# R211J.net
KiCad netlist of a schematic drawn in EAGLE
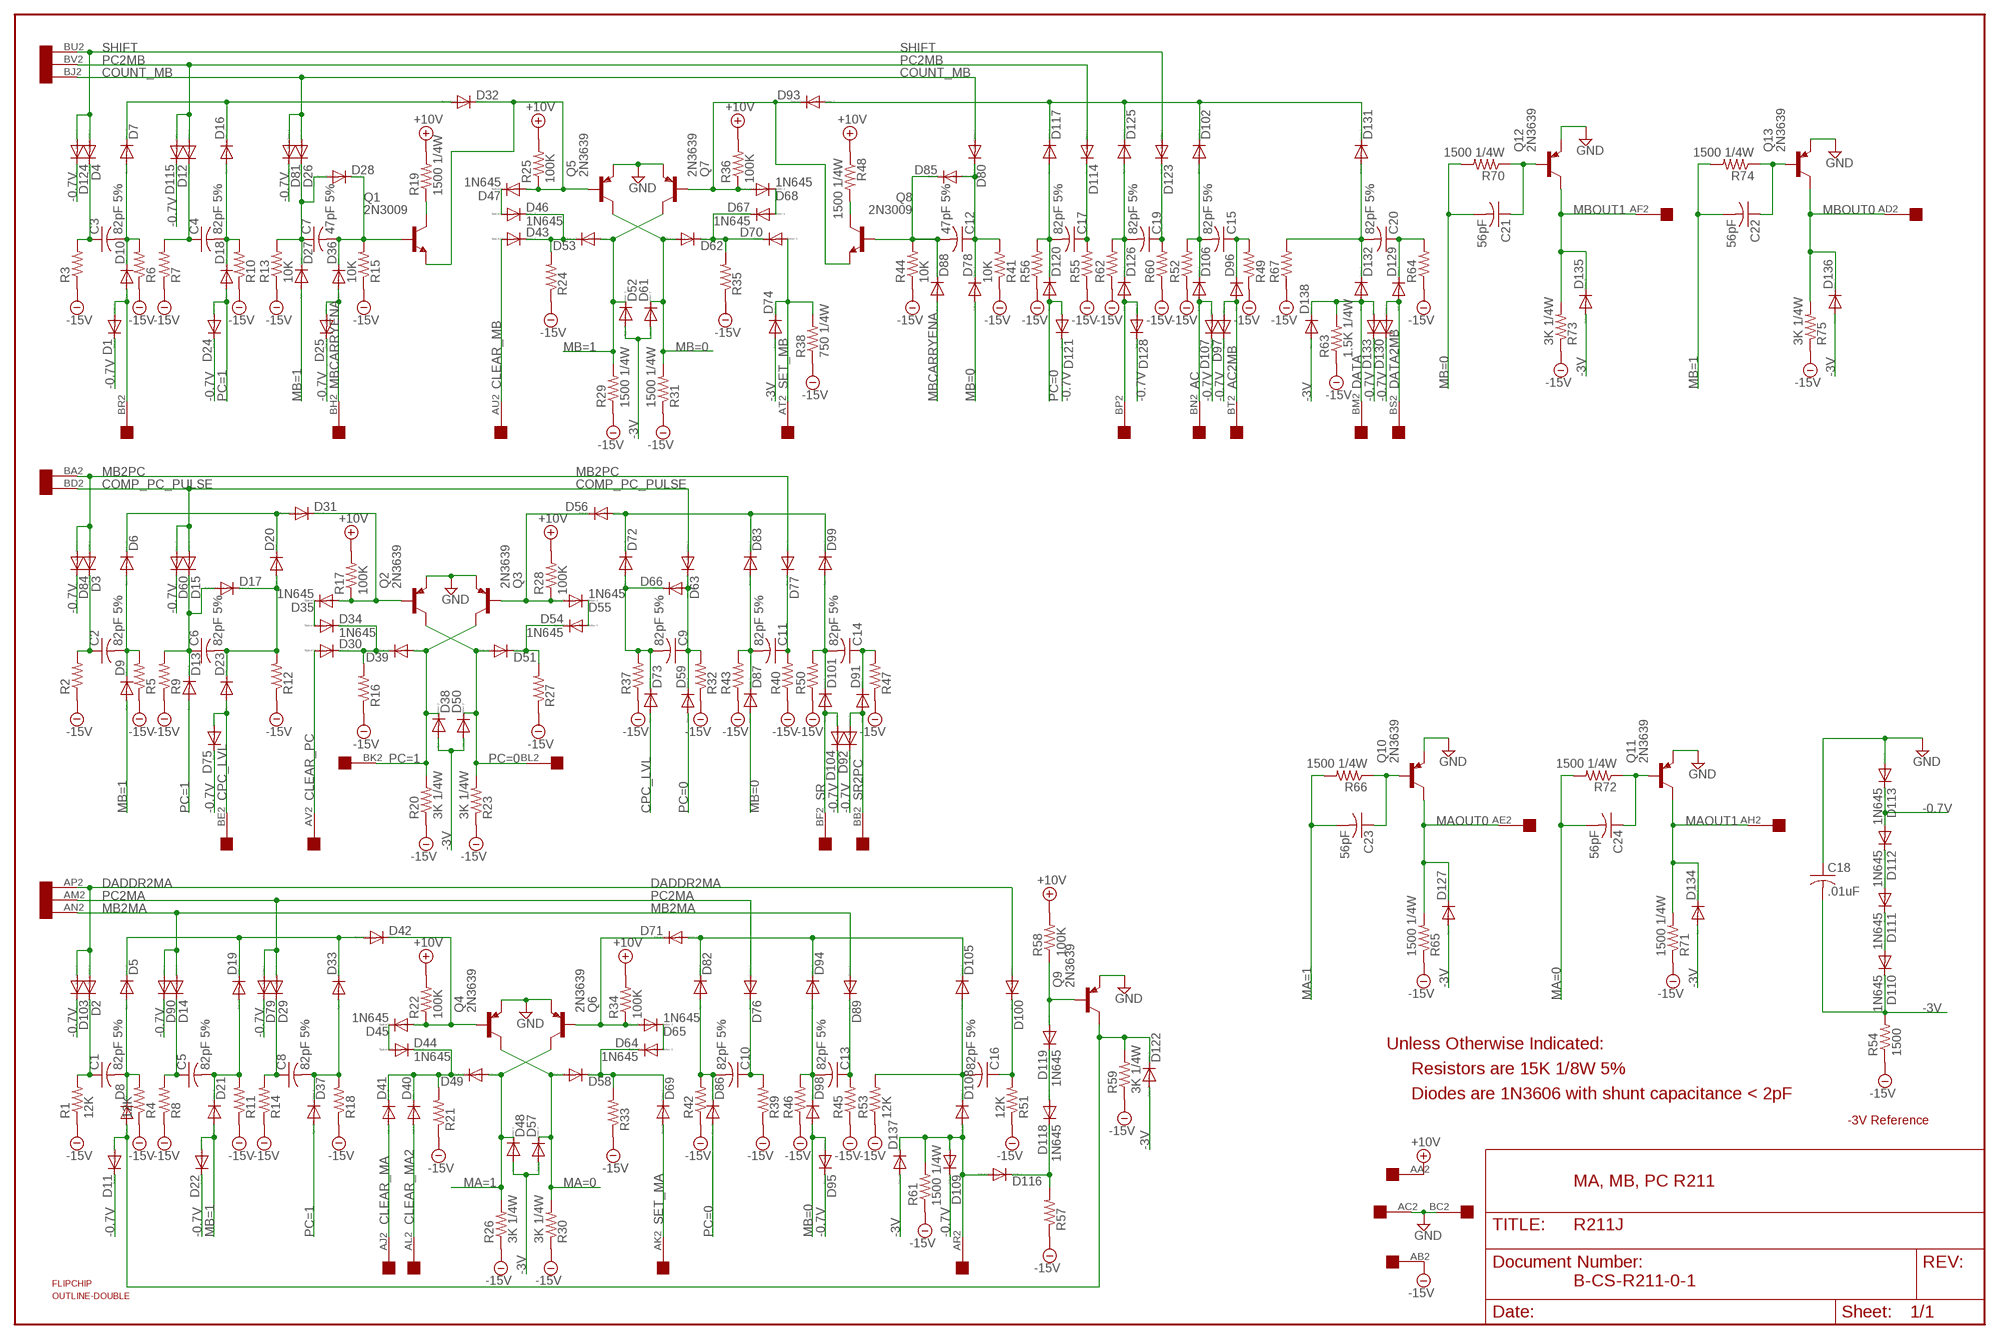
[diagram p0: schematic, sheet 1]

(export (version "E")
  (design (tool "Eeschema 10.0.6"))
  (components
    (comp (ref "C1")
      (value "82pF 5%")
      (footprint "eagle-import:C050-025X075")
      (libsource (lib "eagle-import") (part "C-US050-025X075"))
    )
    (comp (ref "C2")
      (value "82pF 5%")
      (footprint "eagle-import:C050-025X075")
      (libsource (lib "eagle-import") (part "C-US050-025X075"))
    )
    (comp (ref "C3")
      (value "82pF 5%")
      (footprint "eagle-import:C050-025X075")
      (libsource (lib "eagle-import") (part "C-US050-025X075"))
    )
    (comp (ref "C4")
      (value "82pF 5%")
      (footprint "eagle-import:C050-025X075")
      (libsource (lib "eagle-import") (part "C-US050-025X075"))
    )
    (comp (ref "C5")
      (value "82pF 5%")
      (footprint "eagle-import:C050-025X075")
      (libsource (lib "eagle-import") (part "C-US050-025X075"))
    )
    (comp (ref "C6")
      (value "82pF 5%")
      (footprint "eagle-import:C050-025X075")
      (libsource (lib "eagle-import") (part "C-US050-025X075"))
    )
    (comp (ref "C7")
      (value "47pF 5%")
      (footprint "eagle-import:C050-025X075")
      (libsource (lib "eagle-import") (part "C-US050-025X075"))
    )
    (comp (ref "C8")
      (value "82pF 5%")
      (footprint "eagle-import:C050-025X075")
      (libsource (lib "eagle-import") (part "C-US050-025X075"))
    )
    (comp (ref "C9")
      (value "82pF 5%")
      (footprint "eagle-import:C050-025X075")
      (libsource (lib "eagle-import") (part "C-US050-025X075"))
    )
    (comp (ref "C10")
      (value "82pF 5%")
      (footprint "eagle-import:C050-025X075")
      (libsource (lib "eagle-import") (part "C-US050-025X075"))
    )
    (comp (ref "C11")
      (value "82pF 5%")
      (footprint "eagle-import:C050-025X075")
      (libsource (lib "eagle-import") (part "C-US050-025X075"))
    )
    (comp (ref "C12")
      (value "47pF 5%")
      (footprint "eagle-import:C050-025X075")
      (libsource (lib "eagle-import") (part "C-US050-025X075"))
    )
    (comp (ref "C13")
      (value "82pF 5%")
      (footprint "eagle-import:C050-025X075")
      (libsource (lib "eagle-import") (part "C-US050-025X075"))
    )
    (comp (ref "C14")
      (value "82pF 5%")
      (footprint "eagle-import:C050-025X075")
      (libsource (lib "eagle-import") (part "C-US050-025X075"))
    )
    (comp (ref "C15")
      (value "82pF 5%")
      (footprint "eagle-import:C050-025X075")
      (libsource (lib "eagle-import") (part "C-US050-025X075"))
    )
    (comp (ref "C16")
      (value "82pF 5%")
      (footprint "eagle-import:C050-025X075")
      (libsource (lib "eagle-import") (part "C-US050-025X075"))
    )
    (comp (ref "C17")
      (value "82pF 5%")
      (footprint "eagle-import:C050-025X075")
      (libsource (lib "eagle-import") (part "C-US050-025X075"))
    )
    (comp (ref "C18")
      (value ".01uF")
      (footprint "eagle-import:C050-025X075")
      (libsource (lib "eagle-import") (part "C-US050-025X075"))
    )
    (comp (ref "C19")
      (value "82pF 5%")
      (footprint "eagle-import:C050-025X075")
      (libsource (lib "eagle-import") (part "C-US050-025X075"))
    )
    (comp (ref "C20")
      (value "82pF 5%")
      (footprint "eagle-import:C050-025X075")
      (libsource (lib "eagle-import") (part "C-US050-025X075"))
    )
    (comp (ref "C21")
      (value "56pF")
      (footprint "eagle-import:C050-025X075")
      (libsource (lib "eagle-import") (part "C-US050-025X075"))
    )
    (comp (ref "C22")
      (value "56pF")
      (footprint "eagle-import:C050-025X075")
      (libsource (lib "eagle-import") (part "C-US050-025X075"))
    )
    (comp (ref "C23")
      (value "56pF")
      (footprint "eagle-import:C050-025X075")
      (libsource (lib "eagle-import") (part "C-US050-025X075"))
    )
    (comp (ref "C24")
      (value "56pF")
      (footprint "eagle-import:C050-025X075")
      (libsource (lib "eagle-import") (part "C-US050-025X075"))
    )
    (comp (ref "D1")
      (value "1N4148DO35-10")
      (footprint "eagle-import:DO35-10")
      (libsource (lib "eagle-import") (part "1N4148DO35-10"))
    )
    (comp (ref "D2")
      (value "1N4148DO35-10")
      (footprint "eagle-import:DO35-10")
      (libsource (lib "eagle-import") (part "1N4148DO35-10"))
    )
    (comp (ref "D3")
      (value "1N4148DO35-10")
      (footprint "eagle-import:DO35-10")
      (libsource (lib "eagle-import") (part "1N4148DO35-10"))
    )
    (comp (ref "D4")
      (value "1N4148DO35-10")
      (footprint "eagle-import:DO35-10")
      (libsource (lib "eagle-import") (part "1N4148DO35-10"))
    )
    (comp (ref "D5")
      (value "1N4148DO35-10")
      (footprint "eagle-import:DO35-10")
      (libsource (lib "eagle-import") (part "1N4148DO35-10"))
    )
    (comp (ref "D6")
      (value "1N4148DO35-10")
      (footprint "eagle-import:DO35-10")
      (libsource (lib "eagle-import") (part "1N4148DO35-10"))
    )
    (comp (ref "D7")
      (value "1N4148DO35-10")
      (footprint "eagle-import:DO35-10")
      (libsource (lib "eagle-import") (part "1N4148DO35-10"))
    )
    (comp (ref "D8")
      (value "1N4148DO35-10")
      (footprint "eagle-import:DO35-10")
      (libsource (lib "eagle-import") (part "1N4148DO35-10"))
    )
    (comp (ref "D9")
      (value "1N4148DO35-10")
      (footprint "eagle-import:DO35-10")
      (libsource (lib "eagle-import") (part "1N4148DO35-10"))
    )
    (comp (ref "D10")
      (value "1N4148DO35-10")
      (footprint "eagle-import:DO35-10")
      (libsource (lib "eagle-import") (part "1N4148DO35-10"))
    )
    (comp (ref "D11")
      (value "1N4148DO35-10")
      (footprint "eagle-import:DO35-10")
      (libsource (lib "eagle-import") (part "1N4148DO35-10"))
    )
    (comp (ref "D12")
      (value "1N4148DO35-10")
      (footprint "eagle-import:DO35-10")
      (libsource (lib "eagle-import") (part "1N4148DO35-10"))
    )
    (comp (ref "D13")
      (value "1N4148DO35-10")
      (footprint "eagle-import:DO35-10")
      (libsource (lib "eagle-import") (part "1N4148DO35-10"))
    )
    (comp (ref "D14")
      (value "1N4148DO35-10")
      (footprint "eagle-import:DO35-10")
      (libsource (lib "eagle-import") (part "1N4148DO35-10"))
    )
    (comp (ref "D15")
      (value "1N4148DO35-10")
      (footprint "eagle-import:DO35-10")
      (libsource (lib "eagle-import") (part "1N4148DO35-10"))
    )
    (comp (ref "D16")
      (value "1N4148DO35-10")
      (footprint "eagle-import:DO35-10")
      (libsource (lib "eagle-import") (part "1N4148DO35-10"))
    )
    (comp (ref "D17")
      (value "1N4148DO35-10")
      (footprint "eagle-import:DO35-10")
      (libsource (lib "eagle-import") (part "1N4148DO35-10"))
    )
    (comp (ref "D18")
      (value "1N4148DO35-10")
      (footprint "eagle-import:DO35-10")
      (libsource (lib "eagle-import") (part "1N4148DO35-10"))
    )
    (comp (ref "D19")
      (value "1N4148DO35-10")
      (footprint "eagle-import:DO35-10")
      (libsource (lib "eagle-import") (part "1N4148DO35-10"))
    )
    (comp (ref "D20")
      (value "1N4148DO35-10")
      (footprint "eagle-import:DO35-10")
      (libsource (lib "eagle-import") (part "1N4148DO35-10"))
    )
    (comp (ref "D21")
      (value "1N4148DO35-10")
      (footprint "eagle-import:DO35-10")
      (libsource (lib "eagle-import") (part "1N4148DO35-10"))
    )
    (comp (ref "D22")
      (value "1N4148DO35-10")
      (footprint "eagle-import:DO35-10")
      (libsource (lib "eagle-import") (part "1N4148DO35-10"))
    )
    (comp (ref "D23")
      (value "1N4148DO35-10")
      (footprint "eagle-import:DO35-10")
      (libsource (lib "eagle-import") (part "1N4148DO35-10"))
    )
    (comp (ref "D24")
      (value "1N4148DO35-10")
      (footprint "eagle-import:DO35-10")
      (libsource (lib "eagle-import") (part "1N4148DO35-10"))
    )
    (comp (ref "D25")
      (value "1N4148DO35-10")
      (footprint "eagle-import:DO35-10")
      (libsource (lib "eagle-import") (part "1N4148DO35-10"))
    )
    (comp (ref "D26")
      (value "1N4148DO35-10")
      (footprint "eagle-import:DO35-10")
      (libsource (lib "eagle-import") (part "1N4148DO35-10"))
    )
    (comp (ref "D27")
      (value "1N4148DO35-10")
      (footprint "eagle-import:DO35-10")
      (libsource (lib "eagle-import") (part "1N4148DO35-10"))
    )
    (comp (ref "D28")
      (value "1N4148DO35-10")
      (footprint "eagle-import:DO35-10")
      (libsource (lib "eagle-import") (part "1N4148DO35-10"))
    )
    (comp (ref "D29")
      (value "1N4148DO35-10")
      (footprint "eagle-import:DO35-10")
      (libsource (lib "eagle-import") (part "1N4148DO35-10"))
    )
    (comp (ref "D30")
      (value "1N4148DO35-10")
      (footprint "eagle-import:DO35-10")
      (libsource (lib "eagle-import") (part "1N4148DO35-10"))
    )
    (comp (ref "D31")
      (value "1N4148DO35-10")
      (footprint "eagle-import:DO35-10")
      (libsource (lib "eagle-import") (part "1N4148DO35-10"))
    )
    (comp (ref "D32")
      (value "1N4148DO35-10")
      (footprint "eagle-import:DO35-10")
      (libsource (lib "eagle-import") (part "1N4148DO35-10"))
    )
    (comp (ref "D33")
      (value "1N4148DO35-10")
      (footprint "eagle-import:DO35-10")
      (libsource (lib "eagle-import") (part "1N4148DO35-10"))
    )
    (comp (ref "D34")
      (value "1N645")
      (footprint "eagle-import:DO35-10")
      (libsource (lib "eagle-import") (part "1N4148DO35-10"))
    )
    (comp (ref "D35")
      (value "1N645")
      (footprint "eagle-import:DO35-10")
      (libsource (lib "eagle-import") (part "1N4148DO35-10"))
    )
    (comp (ref "D36")
      (value "1N4148DO35-10")
      (footprint "eagle-import:DO35-10")
      (libsource (lib "eagle-import") (part "1N4148DO35-10"))
    )
    (comp (ref "D37")
      (value "1N4148DO35-10")
      (footprint "eagle-import:DO35-10")
      (libsource (lib "eagle-import") (part "1N4148DO35-10"))
    )
    (comp (ref "D38")
      (value "1N4148DO35-10")
      (footprint "eagle-import:DO35-10")
      (libsource (lib "eagle-import") (part "1N4148DO35-10"))
    )
    (comp (ref "D39")
      (value "1N4148DO35-10")
      (footprint "eagle-import:DO35-10")
      (libsource (lib "eagle-import") (part "1N4148DO35-10"))
    )
    (comp (ref "D40")
      (value "1N4148DO35-10")
      (footprint "eagle-import:DO35-10")
      (libsource (lib "eagle-import") (part "1N4148DO35-10"))
    )
    (comp (ref "D41")
      (value "1N4148DO35-10")
      (footprint "eagle-import:DO35-10")
      (libsource (lib "eagle-import") (part "1N4148DO35-10"))
    )
    (comp (ref "D42")
      (value "1N4148DO35-10")
      (footprint "eagle-import:DO35-10")
      (libsource (lib "eagle-import") (part "1N4148DO35-10"))
    )
    (comp (ref "D43")
      (value "1N4148DO35-10")
      (footprint "eagle-import:DO35-10")
      (libsource (lib "eagle-import") (part "1N4148DO35-10"))
    )
    (comp (ref "D44")
      (value "1N645")
      (footprint "eagle-import:DO35-10")
      (libsource (lib "eagle-import") (part "1N4148DO35-10"))
    )
    (comp (ref "D45")
      (value "1N645")
      (footprint "eagle-import:DO35-10")
      (libsource (lib "eagle-import") (part "1N4148DO35-10"))
    )
    (comp (ref "D46")
      (value "1N645")
      (footprint "eagle-import:DO35-10")
      (libsource (lib "eagle-import") (part "1N4148DO35-10"))
    )
    (comp (ref "D47")
      (value "1N645")
      (footprint "eagle-import:DO35-10")
      (libsource (lib "eagle-import") (part "1N4148DO35-10"))
    )
    (comp (ref "D48")
      (value "1N4148DO35-10")
      (footprint "eagle-import:DO35-10")
      (libsource (lib "eagle-import") (part "1N4148DO35-10"))
    )
    (comp (ref "D49")
      (value "1N4148DO35-10")
      (footprint "eagle-import:DO35-10")
      (libsource (lib "eagle-import") (part "1N4148DO35-10"))
    )
    (comp (ref "D50")
      (value "1N4148DO35-10")
      (footprint "eagle-import:DO35-10")
      (libsource (lib "eagle-import") (part "1N4148DO35-10"))
    )
    (comp (ref "D51")
      (value "1N4148DO35-10")
      (footprint "eagle-import:DO35-10")
      (libsource (lib "eagle-import") (part "1N4148DO35-10"))
    )
    (comp (ref "D52")
      (value "1N4148DO35-10")
      (footprint "eagle-import:DO35-10")
      (libsource (lib "eagle-import") (part "1N4148DO35-10"))
    )
    (comp (ref "D53")
      (value "1N4148DO35-10")
      (footprint "eagle-import:DO35-10")
      (libsource (lib "eagle-import") (part "1N4148DO35-10"))
    )
    (comp (ref "D54")
      (value "1N645")
      (footprint "eagle-import:DO35-10")
      (libsource (lib "eagle-import") (part "1N4148DO35-10"))
    )
    (comp (ref "D55")
      (value "1N645")
      (footprint "eagle-import:DO35-10")
      (libsource (lib "eagle-import") (part "1N4148DO35-10"))
    )
    (comp (ref "D56")
      (value "1N4148DO35-10")
      (footprint "eagle-import:DO35-10")
      (libsource (lib "eagle-import") (part "1N4148DO35-10"))
    )
    (comp (ref "D57")
      (value "1N4148DO35-10")
      (footprint "eagle-import:DO35-10")
      (libsource (lib "eagle-import") (part "1N4148DO35-10"))
    )
    (comp (ref "D58")
      (value "1N4148DO35-10")
      (footprint "eagle-import:DO35-10")
      (libsource (lib "eagle-import") (part "1N4148DO35-10"))
    )
    (comp (ref "D59")
      (value "1N4148DO35-10")
      (footprint "eagle-import:DO35-10")
      (libsource (lib "eagle-import") (part "1N4148DO35-10"))
    )
    (comp (ref "D60")
      (value "1N4148DO35-10")
      (footprint "eagle-import:DO35-10")
      (libsource (lib "eagle-import") (part "1N4148DO35-10"))
    )
    (comp (ref "D61")
      (value "1N4148DO35-10")
      (footprint "eagle-import:DO35-10")
      (libsource (lib "eagle-import") (part "1N4148DO35-10"))
    )
    (comp (ref "D62")
      (value "1N4148DO35-10")
      (footprint "eagle-import:DO35-10")
      (libsource (lib "eagle-import") (part "1N4148DO35-10"))
    )
    (comp (ref "D63")
      (value "1N4148DO35-10")
      (footprint "eagle-import:DO35-10")
      (libsource (lib "eagle-import") (part "1N4148DO35-10"))
    )
    (comp (ref "D64")
      (value "1N645")
      (footprint "eagle-import:DO35-10")
      (libsource (lib "eagle-import") (part "1N4148DO35-10"))
    )
    (comp (ref "D65")
      (value "1N645")
      (footprint "eagle-import:DO35-10")
      (libsource (lib "eagle-import") (part "1N4148DO35-10"))
    )
    (comp (ref "D66")
      (value "1N4148DO35-10")
      (footprint "eagle-import:DO35-10")
      (libsource (lib "eagle-import") (part "1N4148DO35-10"))
    )
    (comp (ref "D67")
      (value "1N645")
      (footprint "eagle-import:DO35-10")
      (libsource (lib "eagle-import") (part "1N4148DO35-10"))
    )
    (comp (ref "D68")
      (value "1N645")
      (footprint "eagle-import:DO35-10")
      (libsource (lib "eagle-import") (part "1N4148DO35-10"))
    )
    (comp (ref "D69")
      (value "1N4148DO35-10")
      (footprint "eagle-import:DO35-10")
      (libsource (lib "eagle-import") (part "1N4148DO35-10"))
    )
    (comp (ref "D70")
      (value "1N4148DO35-10")
      (footprint "eagle-import:DO35-10")
      (libsource (lib "eagle-import") (part "1N4148DO35-10"))
    )
    (comp (ref "D71")
      (value "1N4148DO35-10")
      (footprint "eagle-import:DO35-10")
      (libsource (lib "eagle-import") (part "1N4148DO35-10"))
    )
    (comp (ref "D72")
      (value "1N4148DO35-10")
      (footprint "eagle-import:DO35-10")
      (libsource (lib "eagle-import") (part "1N4148DO35-10"))
    )
    (comp (ref "D73")
      (value "1N4148DO35-10")
      (footprint "eagle-import:DO35-10")
      (libsource (lib "eagle-import") (part "1N4148DO35-10"))
    )
    (comp (ref "D74")
      (value "1N4148DO35-10")
      (footprint "eagle-import:DO35-10")
      (libsource (lib "eagle-import") (part "1N4148DO35-10"))
    )
    (comp (ref "D75")
      (value "1N4148DO35-10")
      (footprint "eagle-import:DO35-10")
      (libsource (lib "eagle-import") (part "1N4148DO35-10"))
    )
    (comp (ref "D76")
      (value "1N4148DO35-10")
      (footprint "eagle-import:DO35-10")
      (libsource (lib "eagle-import") (part "1N4148DO35-10"))
    )
    (comp (ref "D77")
      (value "1N4148DO35-10")
      (footprint "eagle-import:DO35-10")
      (libsource (lib "eagle-import") (part "1N4148DO35-10"))
    )
    (comp (ref "D78")
      (value "1N4148DO35-10")
      (footprint "eagle-import:DO35-10")
      (libsource (lib "eagle-import") (part "1N4148DO35-10"))
    )
    (comp (ref "D79")
      (value "1N4148DO35-10")
      (footprint "eagle-import:DO35-10")
      (libsource (lib "eagle-import") (part "1N4148DO35-10"))
    )
    (comp (ref "D80")
      (value "1N4148DO35-10")
      (footprint "eagle-import:DO35-10")
      (libsource (lib "eagle-import") (part "1N4148DO35-10"))
    )
    (comp (ref "D81")
      (value "1N4148DO35-10")
      (footprint "eagle-import:DO35-10")
      (libsource (lib "eagle-import") (part "1N4148DO35-10"))
    )
    (comp (ref "D82")
      (value "1N4148DO35-10")
      (footprint "eagle-import:DO35-10")
      (libsource (lib "eagle-import") (part "1N4148DO35-10"))
    )
    (comp (ref "D83")
      (value "1N4148DO35-10")
      (footprint "eagle-import:DO35-10")
      (libsource (lib "eagle-import") (part "1N4148DO35-10"))
    )
    (comp (ref "D84")
      (value "1N4148DO35-10")
      (footprint "eagle-import:DO35-10")
      (libsource (lib "eagle-import") (part "1N4148DO35-10"))
    )
    (comp (ref "D85")
      (value "1N4148DO35-10")
      (footprint "eagle-import:DO35-10")
      (libsource (lib "eagle-import") (part "1N4148DO35-10"))
    )
    (comp (ref "D86")
      (value "1N4148DO35-10")
      (footprint "eagle-import:DO35-10")
      (libsource (lib "eagle-import") (part "1N4148DO35-10"))
    )
    (comp (ref "D87")
      (value "1N4148DO35-10")
      (footprint "eagle-import:DO35-10")
      (libsource (lib "eagle-import") (part "1N4148DO35-10"))
    )
    (comp (ref "D88")
      (value "1N4148DO35-10")
      (footprint "eagle-import:DO35-10")
      (libsource (lib "eagle-import") (part "1N4148DO35-10"))
    )
    (comp (ref "D89")
      (value "1N4148DO35-10")
      (footprint "eagle-import:DO35-10")
      (libsource (lib "eagle-import") (part "1N4148DO35-10"))
    )
    (comp (ref "D90")
      (value "1N4148DO35-10")
      (footprint "eagle-import:DO35-10")
      (libsource (lib "eagle-import") (part "1N4148DO35-10"))
    )
    (comp (ref "D91")
      (value "1N4148DO35-10")
      (footprint "eagle-import:DO35-10")
      (libsource (lib "eagle-import") (part "1N4148DO35-10"))
    )
    (comp (ref "D92")
      (value "1N4148DO35-10")
      (footprint "eagle-import:DO35-10")
      (libsource (lib "eagle-import") (part "1N4148DO35-10"))
    )
    (comp (ref "D93")
      (value "1N4148DO35-10")
      (footprint "eagle-import:DO35-10")
      (libsource (lib "eagle-import") (part "1N4148DO35-10"))
    )
    (comp (ref "D94")
      (value "1N4148DO35-10")
      (footprint "eagle-import:DO35-10")
      (libsource (lib "eagle-import") (part "1N4148DO35-10"))
    )
    (comp (ref "D95")
      (value "1N4148DO35-10")
      (footprint "eagle-import:DO35-10")
      (libsource (lib "eagle-import") (part "1N4148DO35-10"))
    )
    (comp (ref "D96")
      (value "1N4148DO35-10")
      (footprint "eagle-import:DO35-10")
      (libsource (lib "eagle-import") (part "1N4148DO35-10"))
    )
    (comp (ref "D97")
      (value "1N4148DO35-10")
      (footprint "eagle-import:DO35-10")
      (libsource (lib "eagle-import") (part "1N4148DO35-10"))
    )
    (comp (ref "D98")
      (value "1N4148DO35-10")
      (footprint "eagle-import:DO35-10")
      (libsource (lib "eagle-import") (part "1N4148DO35-10"))
    )
    (comp (ref "D99")
      (value "1N4148DO35-10")
      (footprint "eagle-import:DO35-10")
      (libsource (lib "eagle-import") (part "1N4148DO35-10"))
    )
    (comp (ref "D100")
      (value "1N4148DO35-10")
      (footprint "eagle-import:DO35-10")
      (libsource (lib "eagle-import") (part "1N4148DO35-10"))
    )
    (comp (ref "D101")
      (value "1N4148DO35-10")
      (footprint "eagle-import:DO35-10")
      (libsource (lib "eagle-import") (part "1N4148DO35-10"))
    )
    (comp (ref "D102")
      (value "1N4148DO35-10")
      (footprint "eagle-import:DO35-10")
      (libsource (lib "eagle-import") (part "1N4148DO35-10"))
    )
    (comp (ref "D103")
      (value "1N4148DO35-10")
      (footprint "eagle-import:DO35-10")
      (libsource (lib "eagle-import") (part "1N4148DO35-10"))
    )
    (comp (ref "D104")
      (value "1N4148DO35-10")
      (footprint "eagle-import:DO35-10")
      (libsource (lib "eagle-import") (part "1N4148DO35-10"))
    )
    (comp (ref "D105")
      (value "1N4148DO35-10")
      (footprint "eagle-import:DO35-10")
      (libsource (lib "eagle-import") (part "1N4148DO35-10"))
    )
    (comp (ref "D106")
      (value "1N4148DO35-10")
      (footprint "eagle-import:DO35-10")
      (libsource (lib "eagle-import") (part "1N4148DO35-10"))
    )
    (comp (ref "D107")
      (value "1N4148DO35-10")
      (footprint "eagle-import:DO35-10")
      (libsource (lib "eagle-import") (part "1N4148DO35-10"))
    )
    (comp (ref "D108")
      (value "1N4148DO35-10")
      (footprint "eagle-import:DO35-10")
      (libsource (lib "eagle-import") (part "1N4148DO35-10"))
    )
    (comp (ref "D109")
      (value "1N4148DO35-10")
      (footprint "eagle-import:DO35-10")
      (libsource (lib "eagle-import") (part "1N4148DO35-10"))
    )
    (comp (ref "D110")
      (value "1N645")
      (footprint "eagle-import:DO35-10")
      (libsource (lib "eagle-import") (part "1N4148DO35-10"))
    )
    (comp (ref "D111")
      (value "1N645")
      (footprint "eagle-import:DO35-10")
      (libsource (lib "eagle-import") (part "1N4148DO35-10"))
    )
    (comp (ref "D112")
      (value "1N645")
      (footprint "eagle-import:DO35-10")
      (libsource (lib "eagle-import") (part "1N4148DO35-10"))
    )
    (comp (ref "D113")
      (value "1N645")
      (footprint "eagle-import:DO35-10")
      (libsource (lib "eagle-import") (part "1N4148DO35-10"))
    )
    (comp (ref "D114")
      (value "1N4148DO35-10")
      (footprint "eagle-import:DO35-10")
      (libsource (lib "eagle-import") (part "1N4148DO35-10"))
    )
    (comp (ref "D115")
      (value "1N4148DO35-10")
      (footprint "eagle-import:DO35-10")
      (libsource (lib "eagle-import") (part "1N4148DO35-10"))
    )
    (comp (ref "D116")
      (value "1N4148DO35-10")
      (footprint "eagle-import:DO35-10")
      (libsource (lib "eagle-import") (part "1N4148DO35-10"))
    )
    (comp (ref "D117")
      (value "1N4148DO35-10")
      (footprint "eagle-import:DO35-10")
      (libsource (lib "eagle-import") (part "1N4148DO35-10"))
    )
    (comp (ref "D118")
      (value "1N645")
      (footprint "eagle-import:DO35-10")
      (libsource (lib "eagle-import") (part "1N4148DO35-10"))
    )
    (comp (ref "D119")
      (value "1N645")
      (footprint "eagle-import:DO35-10")
      (libsource (lib "eagle-import") (part "1N4148DO35-10"))
    )
    (comp (ref "D120")
      (value "1N4148DO35-10")
      (footprint "eagle-import:DO35-10")
      (libsource (lib "eagle-import") (part "1N4148DO35-10"))
    )
    (comp (ref "D121")
      (value "1N4148DO35-10")
      (footprint "eagle-import:DO35-10")
      (libsource (lib "eagle-import") (part "1N4148DO35-10"))
    )
    (comp (ref "D122")
      (value "1N4148DO35-10")
      (footprint "eagle-import:DO35-10")
      (libsource (lib "eagle-import") (part "1N4148DO35-10"))
    )
    (comp (ref "D123")
      (value "1N4148DO35-10")
      (footprint "eagle-import:DO35-10")
      (libsource (lib "eagle-import") (part "1N4148DO35-10"))
    )
    (comp (ref "D124")
      (value "1N4148DO35-10")
      (footprint "eagle-import:DO35-10")
      (libsource (lib "eagle-import") (part "1N4148DO35-10"))
    )
    (comp (ref "D125")
      (value "1N4148DO35-10")
      (footprint "eagle-import:DO35-10")
      (libsource (lib "eagle-import") (part "1N4148DO35-10"))
    )
    (comp (ref "D126")
      (value "1N4148DO35-10")
      (footprint "eagle-import:DO35-10")
      (libsource (lib "eagle-import") (part "1N4148DO35-10"))
    )
    (comp (ref "D127")
      (value "1N4148DO35-10")
      (footprint "eagle-import:DO35-10")
      (libsource (lib "eagle-import") (part "1N4148DO35-10"))
    )
    (comp (ref "D128")
      (value "1N4148DO35-10")
      (footprint "eagle-import:DO35-10")
      (libsource (lib "eagle-import") (part "1N4148DO35-10"))
    )
    (comp (ref "D129")
      (value "1N4148DO35-10")
      (footprint "eagle-import:DO35-10")
      (libsource (lib "eagle-import") (part "1N4148DO35-10"))
    )
    (comp (ref "D130")
      (value "1N4148DO35-10")
      (footprint "eagle-import:DO35-10")
      (libsource (lib "eagle-import") (part "1N4148DO35-10"))
    )
    (comp (ref "D131")
      (value "1N4148DO35-10")
      (footprint "eagle-import:DO35-10")
      (libsource (lib "eagle-import") (part "1N4148DO35-10"))
    )
    (comp (ref "D132")
      (value "1N4148DO35-10")
      (footprint "eagle-import:DO35-10")
      (libsource (lib "eagle-import") (part "1N4148DO35-10"))
    )
    (comp (ref "D133")
      (value "1N4148DO35-10")
      (footprint "eagle-import:DO35-10")
      (libsource (lib "eagle-import") (part "1N4148DO35-10"))
    )
    (comp (ref "D134")
      (value "1N4148DO35-10")
      (footprint "eagle-import:DO35-10")
      (libsource (lib "eagle-import") (part "1N4148DO35-10"))
    )
    (comp (ref "D135")
      (value "1N4148DO35-10")
      (footprint "eagle-import:DO35-10")
      (libsource (lib "eagle-import") (part "1N4148DO35-10"))
    )
    (comp (ref "D136")
      (value "1N4148DO35-10")
      (footprint "eagle-import:DO35-10")
      (libsource (lib "eagle-import") (part "1N4148DO35-10"))
    )
    (comp (ref "D137")
      (value "1N4148DO35-10")
      (footprint "eagle-import:DO35-10")
      (libsource (lib "eagle-import") (part "1N4148DO35-10"))
    )
    (comp (ref "D138")
      (value "1N4148DO35-10")
      (footprint "eagle-import:DO35-10")
      (libsource (lib "eagle-import") (part "1N4148DO35-10"))
    )
    (comp (ref "Q1")
      (value "2N3009")
      (footprint "eagle-import:TO5")
      (libsource (lib "eagle-import") (part "2N2102"))
    )
    (comp (ref "Q2")
      (value "2N3639")
      (footprint "eagle-import:TO39")
      (libsource (lib "eagle-import") (part "2N3637"))
    )
    (comp (ref "Q3")
      (value "2N3639")
      (footprint "eagle-import:TO39")
      (libsource (lib "eagle-import") (part "2N3637"))
    )
    (comp (ref "Q4")
      (value "2N3639")
      (footprint "eagle-import:TO39")
      (libsource (lib "eagle-import") (part "2N3637"))
    )
    (comp (ref "Q5")
      (value "2N3639")
      (footprint "eagle-import:TO39")
      (libsource (lib "eagle-import") (part "2N3637"))
    )
    (comp (ref "Q6")
      (value "2N3639")
      (footprint "eagle-import:TO39")
      (libsource (lib "eagle-import") (part "2N3637"))
    )
    (comp (ref "Q7")
      (value "2N3639")
      (footprint "eagle-import:TO39")
      (libsource (lib "eagle-import") (part "2N3637"))
    )
    (comp (ref "Q8")
      (value "2N3009")
      (footprint "eagle-import:TO5")
      (libsource (lib "eagle-import") (part "2N2102"))
    )
    (comp (ref "Q9")
      (value "2N3639")
      (footprint "eagle-import:TO39")
      (libsource (lib "eagle-import") (part "2N3637"))
    )
    (comp (ref "Q10")
      (value "2N3639")
      (footprint "eagle-import:TO39")
      (libsource (lib "eagle-import") (part "2N3637"))
    )
    (comp (ref "Q11")
      (value "2N3639")
      (footprint "eagle-import:TO39")
      (libsource (lib "eagle-import") (part "2N3637"))
    )
    (comp (ref "Q12")
      (value "2N3639")
      (footprint "eagle-import:TO39")
      (libsource (lib "eagle-import") (part "2N3637"))
    )
    (comp (ref "Q13")
      (value "2N3639")
      (footprint "eagle-import:TO39")
      (libsource (lib "eagle-import") (part "2N3637"))
    )
    (comp (ref "R1")
      (value "12K")
      (footprint "eagle-import:0207_10")
      (libsource (lib "eagle-import") (part "R-US_0207/10"))
    )
    (comp (ref "R2")
      (value "R-US_0207/10")
      (footprint "eagle-import:0207_10")
      (libsource (lib "eagle-import") (part "R-US_0207/10"))
    )
    (comp (ref "R3")
      (value "R-US_0207/10")
      (footprint "eagle-import:0207_10")
      (libsource (lib "eagle-import") (part "R-US_0207/10"))
    )
    (comp (ref "R4")
      (value "12K")
      (footprint "eagle-import:0207_10")
      (libsource (lib "eagle-import") (part "R-US_0207/10"))
    )
    (comp (ref "R5")
      (value "R-US_0207/10")
      (footprint "eagle-import:0207_10")
      (libsource (lib "eagle-import") (part "R-US_0207/10"))
    )
    (comp (ref "R6")
      (value "R-US_0207/10")
      (footprint "eagle-import:0207_10")
      (libsource (lib "eagle-import") (part "R-US_0207/10"))
    )
    (comp (ref "R7")
      (value "R-US_0207/10")
      (footprint "eagle-import:0207_10")
      (libsource (lib "eagle-import") (part "R-US_0207/10"))
    )
    (comp (ref "R8")
      (value "R-US_0207/10")
      (footprint "eagle-import:0207_10")
      (libsource (lib "eagle-import") (part "R-US_0207/10"))
    )
    (comp (ref "R9")
      (value "R-US_0207/10")
      (footprint "eagle-import:0207_10")
      (libsource (lib "eagle-import") (part "R-US_0207/10"))
    )
    (comp (ref "R10")
      (value "R-US_0207/10")
      (footprint "eagle-import:0207_10")
      (libsource (lib "eagle-import") (part "R-US_0207/10"))
    )
    (comp (ref "R11")
      (value "R-US_0207/10")
      (footprint "eagle-import:0207_10")
      (libsource (lib "eagle-import") (part "R-US_0207/10"))
    )
    (comp (ref "R12")
      (value "R-US_0207/10")
      (footprint "eagle-import:0207_10")
      (libsource (lib "eagle-import") (part "R-US_0207/10"))
    )
    (comp (ref "R13")
      (value "10K")
      (footprint "eagle-import:0207_10")
      (libsource (lib "eagle-import") (part "R-US_0207/10"))
    )
    (comp (ref "R14")
      (value "R-US_0207/10")
      (footprint "eagle-import:0207_10")
      (libsource (lib "eagle-import") (part "R-US_0207/10"))
    )
    (comp (ref "R15")
      (value "10K")
      (footprint "eagle-import:0207_10")
      (libsource (lib "eagle-import") (part "R-US_0207/10"))
    )
    (comp (ref "R16")
      (value "R-US_0207/10")
      (footprint "eagle-import:0207_10")
      (libsource (lib "eagle-import") (part "R-US_0207/10"))
    )
    (comp (ref "R17")
      (value "100K")
      (footprint "eagle-import:0207_10")
      (libsource (lib "eagle-import") (part "R-US_0207/10"))
    )
    (comp (ref "R18")
      (value "R-US_0207/10")
      (footprint "eagle-import:0207_10")
      (libsource (lib "eagle-import") (part "R-US_0207/10"))
    )
    (comp (ref "R19")
      (value "1500 1/4W")
      (footprint "eagle-import:0207_10")
      (libsource (lib "eagle-import") (part "R-US_0207/10"))
    )
    (comp (ref "R20")
      (value "3K 1/4W")
      (footprint "eagle-import:0207_10")
      (libsource (lib "eagle-import") (part "R-US_0207/10"))
    )
    (comp (ref "R21")
      (value "R-US_0207/10")
      (footprint "eagle-import:0207_10")
      (libsource (lib "eagle-import") (part "R-US_0207/10"))
    )
    (comp (ref "R22")
      (value "100K")
      (footprint "eagle-import:0207_10")
      (libsource (lib "eagle-import") (part "R-US_0207/10"))
    )
    (comp (ref "R23")
      (value "3K 1/4W")
      (footprint "eagle-import:0207_10")
      (libsource (lib "eagle-import") (part "R-US_0207/10"))
    )
    (comp (ref "R24")
      (value "R-US_0207/10")
      (footprint "eagle-import:0207_10")
      (libsource (lib "eagle-import") (part "R-US_0207/10"))
    )
    (comp (ref "R25")
      (value "100K")
      (footprint "eagle-import:0207_10")
      (libsource (lib "eagle-import") (part "R-US_0207/10"))
    )
    (comp (ref "R26")
      (value "3K 1/4W")
      (footprint "eagle-import:0207_10")
      (libsource (lib "eagle-import") (part "R-US_0207/10"))
    )
    (comp (ref "R27")
      (value "R-US_0207/10")
      (footprint "eagle-import:0207_10")
      (libsource (lib "eagle-import") (part "R-US_0207/10"))
    )
    (comp (ref "R28")
      (value "100K")
      (footprint "eagle-import:0207_10")
      (libsource (lib "eagle-import") (part "R-US_0207/10"))
    )
    (comp (ref "R29")
      (value "1500 1/4W")
      (footprint "eagle-import:0207_10")
      (libsource (lib "eagle-import") (part "R-US_0207/10"))
    )
    (comp (ref "R30")
      (value "3K 1/4W")
      (footprint "eagle-import:0207_10")
      (libsource (lib "eagle-import") (part "R-US_0207/10"))
    )
    (comp (ref "R31")
      (value "1500 1/4W")
      (footprint "eagle-import:0207_10")
      (libsource (lib "eagle-import") (part "R-US_0207/10"))
    )
    (comp (ref "R32")
      (value "R-US_0207/10")
      (footprint "eagle-import:0207_10")
      (libsource (lib "eagle-import") (part "R-US_0207/10"))
    )
    (comp (ref "R33")
      (value "R-US_0207/10")
      (footprint "eagle-import:0207_10")
      (libsource (lib "eagle-import") (part "R-US_0207/10"))
    )
    (comp (ref "R34")
      (value "100K")
      (footprint "eagle-import:0207_10")
      (libsource (lib "eagle-import") (part "R-US_0207/10"))
    )
    (comp (ref "R35")
      (value "R-US_0207/10")
      (footprint "eagle-import:0207_10")
      (libsource (lib "eagle-import") (part "R-US_0207/10"))
    )
    (comp (ref "R36")
      (value "100K")
      (footprint "eagle-import:0207_10")
      (libsource (lib "eagle-import") (part "R-US_0207/10"))
    )
    (comp (ref "R37")
      (value "R-US_0207/10")
      (footprint "eagle-import:0207_10")
      (libsource (lib "eagle-import") (part "R-US_0207/10"))
    )
    (comp (ref "R38")
      (value "750 1/4W")
      (footprint "eagle-import:0207_10")
      (libsource (lib "eagle-import") (part "R-US_0207/10"))
    )
    (comp (ref "R39")
      (value "R-US_0207/10")
      (footprint "eagle-import:0207_10")
      (libsource (lib "eagle-import") (part "R-US_0207/10"))
    )
    (comp (ref "R40")
      (value "R-US_0207/10")
      (footprint "eagle-import:0207_10")
      (libsource (lib "eagle-import") (part "R-US_0207/10"))
    )
    (comp (ref "R41")
      (value "10K")
      (footprint "eagle-import:0207_10")
      (libsource (lib "eagle-import") (part "R-US_0207/10"))
    )
    (comp (ref "R42")
      (value "R-US_0207/10")
      (footprint "eagle-import:0207_10")
      (libsource (lib "eagle-import") (part "R-US_0207/10"))
    )
    (comp (ref "R43")
      (value "R-US_0207/10")
      (footprint "eagle-import:0207_10")
      (libsource (lib "eagle-import") (part "R-US_0207/10"))
    )
    (comp (ref "R44")
      (value "10K")
      (footprint "eagle-import:0207_10")
      (libsource (lib "eagle-import") (part "R-US_0207/10"))
    )
    (comp (ref "R45")
      (value "R-US_0207/10")
      (footprint "eagle-import:0207_10")
      (libsource (lib "eagle-import") (part "R-US_0207/10"))
    )
    (comp (ref "R46")
      (value "R-US_0207/10")
      (footprint "eagle-import:0207_10")
      (libsource (lib "eagle-import") (part "R-US_0207/10"))
    )
    (comp (ref "R47")
      (value "R-US_0207/10")
      (footprint "eagle-import:0207_10")
      (libsource (lib "eagle-import") (part "R-US_0207/10"))
    )
    (comp (ref "R48")
      (value "1500 1/4W")
      (footprint "eagle-import:0207_10")
      (libsource (lib "eagle-import") (part "R-US_0207/10"))
    )
    (comp (ref "R49")
      (value "R-US_0207/10")
      (footprint "eagle-import:0207_10")
      (libsource (lib "eagle-import") (part "R-US_0207/10"))
    )
    (comp (ref "R50")
      (value "R-US_0207/10")
      (footprint "eagle-import:0207_10")
      (libsource (lib "eagle-import") (part "R-US_0207/10"))
    )
    (comp (ref "R51")
      (value "12K")
      (footprint "eagle-import:0207_10")
      (libsource (lib "eagle-import") (part "R-US_0207/10"))
    )
    (comp (ref "R52")
      (value "R-US_0207/10")
      (footprint "eagle-import:0207_10")
      (libsource (lib "eagle-import") (part "R-US_0207/10"))
    )
    (comp (ref "R53")
      (value "12K")
      (footprint "eagle-import:0207_10")
      (libsource (lib "eagle-import") (part "R-US_0207/10"))
    )
    (comp (ref "R54")
      (value "1500")
      (footprint "eagle-import:0207_10")
      (libsource (lib "eagle-import") (part "R-US_0207/10"))
    )
    (comp (ref "R55")
      (value "R-US_0207/10")
      (footprint "eagle-import:0207_10")
      (libsource (lib "eagle-import") (part "R-US_0207/10"))
    )
    (comp (ref "R56")
      (value "R-US_0207/10")
      (footprint "eagle-import:0207_10")
      (libsource (lib "eagle-import") (part "R-US_0207/10"))
    )
    (comp (ref "R57")
      (value "R-US_0207/10")
      (footprint "eagle-import:0207_10")
      (libsource (lib "eagle-import") (part "R-US_0207/10"))
    )
    (comp (ref "R58")
      (value "100K")
      (footprint "eagle-import:0207_10")
      (libsource (lib "eagle-import") (part "R-US_0207/10"))
    )
    (comp (ref "R59")
      (value "3K 1/4W")
      (footprint "eagle-import:0207_10")
      (libsource (lib "eagle-import") (part "R-US_0207/10"))
    )
    (comp (ref "R60")
      (value "R-US_0207/10")
      (footprint "eagle-import:0207_10")
      (libsource (lib "eagle-import") (part "R-US_0207/10"))
    )
    (comp (ref "R61")
      (value "1500 1/4W")
      (footprint "eagle-import:0207_10")
      (libsource (lib "eagle-import") (part "R-US_0207/10"))
    )
    (comp (ref "R62")
      (value "R-US_0207/10")
      (footprint "eagle-import:0207_10")
      (libsource (lib "eagle-import") (part "R-US_0207/10"))
    )
    (comp (ref "R63")
      (value "1.5K 1/4W")
      (footprint "eagle-import:0207_10")
      (libsource (lib "eagle-import") (part "R-US_0207/10"))
    )
    (comp (ref "R64")
      (value "R-US_0207/10")
      (footprint "eagle-import:0207_10")
      (libsource (lib "eagle-import") (part "R-US_0207/10"))
    )
    (comp (ref "R65")
      (value "1500 1/4W")
      (footprint "eagle-import:0207_10")
      (libsource (lib "eagle-import") (part "R-US_0207/10"))
    )
    (comp (ref "R66")
      (value "1500 1/4W")
      (footprint "eagle-import:0207_10")
      (libsource (lib "eagle-import") (part "R-US_0207/10"))
    )
    (comp (ref "R67")
      (value "R-US_0207/10")
      (footprint "eagle-import:0207_10")
      (libsource (lib "eagle-import") (part "R-US_0207/10"))
    )
    (comp (ref "R70")
      (value "1500 1/4W")
      (footprint "eagle-import:0207_10")
      (libsource (lib "eagle-import") (part "R-US_0207/10"))
    )
    (comp (ref "R71")
      (value "1500 1/4W")
      (footprint "eagle-import:0207_10")
      (libsource (lib "eagle-import") (part "R-US_0207/10"))
    )
    (comp (ref "R72")
      (value "1500 1/4W")
      (footprint "eagle-import:0207_10")
      (libsource (lib "eagle-import") (part "R-US_0207/10"))
    )
    (comp (ref "R73")
      (value "3K 1/4W")
      (footprint "eagle-import:0207_10")
      (libsource (lib "eagle-import") (part "R-US_0207/10"))
    )
    (comp (ref "R74")
      (value "1500 1/4W")
      (footprint "eagle-import:0207_10")
      (libsource (lib "eagle-import") (part "R-US_0207/10"))
    )
    (comp (ref "R75")
      (value "3K 1/4W")
      (footprint "eagle-import:0207_10")
      (libsource (lib "eagle-import") (part "R-US_0207/10"))
    )
    (comp (ref "U$1")
      (value "DOUBLE")
      (footprint "eagle-import:EDGE-CON4")
      (libsource (lib "eagle-import") (part "DOUBLE"))
    )
    (comp (ref "U$2")
      (value "FLIPCHIP")
      (footprint "eagle-import:FLIPCHIP")
      (libsource (lib "eagle-import") (part "FLIPCHIP"))
    )
    (comp (ref "U$3")
      (value "OUTLINE-DOUBLE")
      (footprint "eagle-import:DOUBLE")
      (libsource (lib "eagle-import") (part "OUTLINE-DOUBLE"))
    )
  )
  (nets
    (net (code "1") (name "+10V") (class "Default")
      (node (ref "R17") (pin "2") (pinfunction "2_2") (pintype "passive"))
      (node (ref "R19") (pin "2") (pinfunction "2_2") (pintype "passive"))
      (node (ref "R22") (pin "2") (pinfunction "2_2") (pintype "passive"))
      (node (ref "R25") (pin "2") (pinfunction "2_2") (pintype "passive"))
      (node (ref "R28") (pin "2") (pinfunction "2_2") (pintype "passive"))
      (node (ref "R34") (pin "2") (pinfunction "2_2") (pintype "passive"))
      (node (ref "R36") (pin "2") (pinfunction "2_2") (pintype "passive"))
      (node (ref "R48") (pin "1") (pinfunction "1_1") (pintype "passive"))
      (node (ref "R58") (pin "2") (pinfunction "2_2") (pintype "passive"))
      (node (ref "U$1") (pin "AA2") (pinfunction "1_AA2") (pintype "bidirectional"))
    )
    (net (code "2") (name "-15V") (class "Default")
      (node (ref "R1") (pin "1") (pinfunction "1_1") (pintype "passive"))
      (node (ref "R10") (pin "1") (pinfunction "1_1") (pintype "passive"))
      (node (ref "R11") (pin "1") (pinfunction "1_1") (pintype "passive"))
      (node (ref "R12") (pin "1") (pinfunction "1_1") (pintype "passive"))
      (node (ref "R13") (pin "1") (pinfunction "1_1") (pintype "passive"))
      (node (ref "R14") (pin "1") (pinfunction "1_1") (pintype "passive"))
      (node (ref "R15") (pin "1") (pinfunction "1_1") (pintype "passive"))
      (node (ref "R16") (pin "1") (pinfunction "1_1") (pintype "passive"))
      (node (ref "R18") (pin "1") (pinfunction "1_1") (pintype "passive"))
      (node (ref "R2") (pin "1") (pinfunction "1_1") (pintype "passive"))
      (node (ref "R20") (pin "1") (pinfunction "1_1") (pintype "passive"))
      (node (ref "R21") (pin "1") (pinfunction "1_1") (pintype "passive"))
      (node (ref "R23") (pin "1") (pinfunction "1_1") (pintype "passive"))
      (node (ref "R24") (pin "1") (pinfunction "1_1") (pintype "passive"))
      (node (ref "R26") (pin "1") (pinfunction "1_1") (pintype "passive"))
      (node (ref "R27") (pin "1") (pinfunction "1_1") (pintype "passive"))
      (node (ref "R29") (pin "1") (pinfunction "1_1") (pintype "passive"))
      (node (ref "R3") (pin "1") (pinfunction "1_1") (pintype "passive"))
      (node (ref "R30") (pin "1") (pinfunction "1_1") (pintype "passive"))
      (node (ref "R31") (pin "1") (pinfunction "1_1") (pintype "passive"))
      (node (ref "R32") (pin "1") (pinfunction "1_1") (pintype "passive"))
      (node (ref "R33") (pin "1") (pinfunction "1_1") (pintype "passive"))
      (node (ref "R35") (pin "1") (pinfunction "1_1") (pintype "passive"))
      (node (ref "R37") (pin "1") (pinfunction "1_1") (pintype "passive"))
      (node (ref "R38") (pin "1") (pinfunction "1_1") (pintype "passive"))
      (node (ref "R39") (pin "1") (pinfunction "1_1") (pintype "passive"))
      (node (ref "R4") (pin "1") (pinfunction "1_1") (pintype "passive"))
      (node (ref "R40") (pin "1") (pinfunction "1_1") (pintype "passive"))
      (node (ref "R41") (pin "1") (pinfunction "1_1") (pintype "passive"))
      (node (ref "R42") (pin "1") (pinfunction "1_1") (pintype "passive"))
      (node (ref "R43") (pin "1") (pinfunction "1_1") (pintype "passive"))
      (node (ref "R44") (pin "1") (pinfunction "1_1") (pintype "passive"))
      (node (ref "R45") (pin "1") (pinfunction "1_1") (pintype "passive"))
      (node (ref "R46") (pin "1") (pinfunction "1_1") (pintype "passive"))
      (node (ref "R47") (pin "1") (pinfunction "1_1") (pintype "passive"))
      (node (ref "R49") (pin "1") (pinfunction "1_1") (pintype "passive"))
      (node (ref "R5") (pin "1") (pinfunction "1_1") (pintype "passive"))
      (node (ref "R50") (pin "1") (pinfunction "1_1") (pintype "passive"))
      (node (ref "R51") (pin "1") (pinfunction "1_1") (pintype "passive"))
      (node (ref "R52") (pin "1") (pinfunction "1_1") (pintype "passive"))
      (node (ref "R53") (pin "1") (pinfunction "1_1") (pintype "passive"))
      (node (ref "R54") (pin "1") (pinfunction "1_1") (pintype "passive"))
      (node (ref "R55") (pin "1") (pinfunction "1_1") (pintype "passive"))
      (node (ref "R56") (pin "1") (pinfunction "1_1") (pintype "passive"))
      (node (ref "R57") (pin "1") (pinfunction "1_1") (pintype "passive"))
      (node (ref "R59") (pin "1") (pinfunction "1_1") (pintype "passive"))
      (node (ref "R6") (pin "1") (pinfunction "1_1") (pintype "passive"))
      (node (ref "R60") (pin "1") (pinfunction "1_1") (pintype "passive"))
      (node (ref "R61") (pin "1") (pinfunction "1_1") (pintype "passive"))
      (node (ref "R62") (pin "1") (pinfunction "1_1") (pintype "passive"))
      (node (ref "R63") (pin "1") (pinfunction "1_1") (pintype "passive"))
      (node (ref "R64") (pin "1") (pinfunction "1_1") (pintype "passive"))
      (node (ref "R65") (pin "1") (pinfunction "1_1") (pintype "passive"))
      (node (ref "R67") (pin "1") (pinfunction "1_1") (pintype "passive"))
      (node (ref "R7") (pin "1") (pinfunction "1_1") (pintype "passive"))
      (node (ref "R71") (pin "1") (pinfunction "1_1") (pintype "passive"))
      (node (ref "R73") (pin "1") (pinfunction "1_1") (pintype "passive"))
      (node (ref "R75") (pin "1") (pinfunction "1_1") (pintype "passive"))
      (node (ref "R8") (pin "1") (pinfunction "1_1") (pintype "passive"))
      (node (ref "R9") (pin "1") (pinfunction "1_1") (pintype "passive"))
      (node (ref "U$1") (pin "AB2") (pinfunction "1_AB2") (pintype "bidirectional"))
    )
    (net (code "3") (name "/-0.7V") (class "Default")
      (node (ref "D1") (pin "C") (pinfunction "C_C") (pintype "passive"))
      (node (ref "D103") (pin "C") (pinfunction "C_C") (pintype "passive"))
      (node (ref "D104") (pin "C") (pinfunction "C_C") (pintype "passive"))
      (node (ref "D107") (pin "C") (pinfunction "C_C") (pintype "passive"))
      (node (ref "D109") (pin "C") (pinfunction "C_C") (pintype "passive"))
      (node (ref "D11") (pin "C") (pinfunction "C_C") (pintype "passive"))
      (node (ref "D112") (pin "A") (pinfunction "A_A") (pintype "passive"))
      (node (ref "D113") (pin "C") (pinfunction "C_C") (pintype "passive"))
      (node (ref "D115") (pin "C") (pinfunction "C_C") (pintype "passive"))
      (node (ref "D121") (pin "C") (pinfunction "C_C") (pintype "passive"))
      (node (ref "D124") (pin "C") (pinfunction "C_C") (pintype "passive"))
      (node (ref "D128") (pin "C") (pinfunction "C_C") (pintype "passive"))
      (node (ref "D130") (pin "C") (pinfunction "C_C") (pintype "passive"))
      (node (ref "D133") (pin "C") (pinfunction "C_C") (pintype "passive"))
      (node (ref "D22") (pin "C") (pinfunction "C_C") (pintype "passive"))
      (node (ref "D24") (pin "C") (pinfunction "C_C") (pintype "passive"))
      (node (ref "D25") (pin "C") (pinfunction "C_C") (pintype "passive"))
      (node (ref "D60") (pin "C") (pinfunction "C_C") (pintype "passive"))
      (node (ref "D75") (pin "C") (pinfunction "C_C") (pintype "passive"))
      (node (ref "D79") (pin "C") (pinfunction "C_C") (pintype "passive"))
      (node (ref "D81") (pin "C") (pinfunction "C_C") (pintype "passive"))
      (node (ref "D84") (pin "C") (pinfunction "C_C") (pintype "passive"))
      (node (ref "D90") (pin "C") (pinfunction "C_C") (pintype "passive"))
      (node (ref "D92") (pin "C") (pinfunction "C_C") (pintype "passive"))
      (node (ref "D95") (pin "C") (pinfunction "C_C") (pintype "passive"))
      (node (ref "D97") (pin "C") (pinfunction "C_C") (pintype "passive"))
    )
    (net (code "4") (name "/-3V") (class "Default")
      (node (ref "C18") (pin "2") (pinfunction "2_2") (pintype "passive"))
      (node (ref "D110") (pin "C") (pinfunction "C_C") (pintype "passive"))
      (node (ref "D122") (pin "A") (pinfunction "A_A") (pintype "passive"))
      (node (ref "D127") (pin "A") (pinfunction "A_A") (pintype "passive"))
      (node (ref "D134") (pin "A") (pinfunction "A_A") (pintype "passive"))
      (node (ref "D135") (pin "A") (pinfunction "A_A") (pintype "passive"))
      (node (ref "D136") (pin "A") (pinfunction "A_A") (pintype "passive"))
      (node (ref "D137") (pin "A") (pinfunction "A_A") (pintype "passive"))
      (node (ref "D138") (pin "A") (pinfunction "A_A") (pintype "passive"))
      (node (ref "D38") (pin "A") (pinfunction "A_A") (pintype "passive"))
      (node (ref "D48") (pin "A") (pinfunction "A_A") (pintype "passive"))
      (node (ref "D50") (pin "A") (pinfunction "A_A") (pintype "passive"))
      (node (ref "D52") (pin "A") (pinfunction "A_A") (pintype "passive"))
      (node (ref "D57") (pin "A") (pinfunction "A_A") (pintype "passive"))
      (node (ref "D61") (pin "A") (pinfunction "A_A") (pintype "passive"))
      (node (ref "D74") (pin "A") (pinfunction "A_A") (pintype "passive"))
      (node (ref "R54") (pin "2") (pinfunction "2_2") (pintype "passive"))
    )
    (net (code "5") (name "/AC") (class "Default")
      (node (ref "D106") (pin "A") (pinfunction "A_A") (pintype "passive"))
      (node (ref "D107") (pin "A") (pinfunction "A_A") (pintype "passive"))
      (node (ref "U$1") (pin "BN2") (pinfunction "1_BN2") (pintype "bidirectional"))
    )
    (net (code "6") (name "/AC2MB") (class "Default")
      (node (ref "D96") (pin "A") (pinfunction "A_A") (pintype "passive"))
      (node (ref "D97") (pin "A") (pinfunction "A_A") (pintype "passive"))
      (node (ref "U$1") (pin "BT2") (pinfunction "1_BT2") (pintype "bidirectional"))
    )
    (net (code "7") (name "/CLEAR_MA") (class "Default")
      (node (ref "D41") (pin "A") (pinfunction "A_A") (pintype "passive"))
      (node (ref "U$1") (pin "AJ2") (pinfunction "1_AJ2") (pintype "bidirectional"))
    )
    (net (code "8") (name "/CLEAR_MA2") (class "Default")
      (node (ref "D40") (pin "A") (pinfunction "A_A") (pintype "passive"))
      (node (ref "U$1") (pin "AL2") (pinfunction "1_AL2") (pintype "bidirectional"))
    )
    (net (code "9") (name "/CLEAR_MB") (class "Default")
      (node (ref "D43") (pin "A") (pinfunction "A_A") (pintype "passive"))
      (node (ref "U$1") (pin "AU2") (pinfunction "1_AU2") (pintype "bidirectional"))
    )
    (net (code "10") (name "/CLEAR_PC") (class "Default")
      (node (ref "D30") (pin "A") (pinfunction "A_A") (pintype "passive"))
      (node (ref "U$1") (pin "AV2") (pinfunction "1_AV2") (pintype "bidirectional"))
    )
    (net (code "11") (name "/COMP_PC_PULSE") (class "Default")
      (node (ref "D15") (pin "A") (pinfunction "A_A") (pintype "passive"))
      (node (ref "D60") (pin "A") (pinfunction "A_A") (pintype "passive"))
      (node (ref "D63") (pin "A") (pinfunction "A_A") (pintype "passive"))
      (node (ref "U$1") (pin "BD2") (pinfunction "1_BD2") (pintype "bidirectional"))
    )
    (net (code "12") (name "/COUNT_MB") (class "Default")
      (node (ref "D26") (pin "A") (pinfunction "A_A") (pintype "passive"))
      (node (ref "D80") (pin "A") (pinfunction "A_A") (pintype "passive"))
      (node (ref "D81") (pin "A") (pinfunction "A_A") (pintype "passive"))
      (node (ref "U$1") (pin "BJ2") (pinfunction "1_BJ2") (pintype "bidirectional"))
    )
    (net (code "13") (name "/CPC_LVL") (class "Default")
      (node (ref "D23") (pin "A") (pinfunction "A_A") (pintype "passive"))
      (node (ref "D73") (pin "A") (pinfunction "A_A") (pintype "passive"))
      (node (ref "D75") (pin "A") (pinfunction "A_A") (pintype "passive"))
      (node (ref "U$1") (pin "BE2") (pinfunction "1_BE2") (pintype "bidirectional"))
    )
    (net (code "14") (name "/DADDR2MA") (class "Default")
      (node (ref "D100") (pin "A") (pinfunction "A_A") (pintype "passive"))
      (node (ref "D103") (pin "A") (pinfunction "A_A") (pintype "passive"))
      (node (ref "D2") (pin "A") (pinfunction "A_A") (pintype "passive"))
      (node (ref "U$1") (pin "AP2") (pinfunction "1_AP2") (pintype "bidirectional"))
    )
    (net (code "15") (name "/DATA") (class "Default")
      (node (ref "D132") (pin "A") (pinfunction "A_A") (pintype "passive"))
      (node (ref "D133") (pin "A") (pinfunction "A_A") (pintype "passive"))
      (node (ref "D138") (pin "C") (pinfunction "C_C") (pintype "passive"))
      (node (ref "R63") (pin "2") (pinfunction "2_2") (pintype "passive"))
      (node (ref "U$1") (pin "BM2") (pinfunction "1_BM2") (pintype "bidirectional"))
    )
    (net (code "16") (name "/DATA2MB") (class "Default")
      (node (ref "D129") (pin "A") (pinfunction "A_A") (pintype "passive"))
      (node (ref "D130") (pin "A") (pinfunction "A_A") (pintype "passive"))
      (node (ref "U$1") (pin "BS2") (pinfunction "1_BS2") (pintype "bidirectional"))
    )
    (net (code "17") (name "/MA=0") (class "Default")
      (node (ref "C24") (pin "2") (pinfunction "2_2") (pintype "passive"))
      (node (ref "D57") (pin "C") (pinfunction "C_C") (pintype "passive"))
      (node (ref "D58") (pin "A") (pinfunction "A_A") (pintype "passive"))
      (node (ref "Q4") (pin "3") (pinfunction "C_3") (pintype "passive"))
      (node (ref "R30") (pin "2") (pinfunction "2_2") (pintype "passive"))
      (node (ref "R72") (pin "2") (pinfunction "2_2") (pintype "passive"))
    )
    (net (code "18") (name "/MA=1") (class "Default")
      (node (ref "C23") (pin "2") (pinfunction "2_2") (pintype "passive"))
      (node (ref "D48") (pin "C") (pinfunction "C_C") (pintype "passive"))
      (node (ref "D49") (pin "A") (pinfunction "A_A") (pintype "passive"))
      (node (ref "Q6") (pin "3") (pinfunction "C_3") (pintype "passive"))
      (node (ref "R26") (pin "2") (pinfunction "2_2") (pintype "passive"))
      (node (ref "R66") (pin "2") (pinfunction "2_2") (pintype "passive"))
    )
    (net (code "19") (name "/MAOUT0") (class "Default")
      (node (ref "D127") (pin "C") (pinfunction "C_C") (pintype "passive"))
      (node (ref "Q10") (pin "3") (pinfunction "C_3") (pintype "passive"))
      (node (ref "R65") (pin "2") (pinfunction "2_2") (pintype "passive"))
      (node (ref "U$1") (pin "AE2") (pinfunction "1_AE2") (pintype "bidirectional"))
    )
    (net (code "20") (name "/MAOUT1") (class "Default")
      (node (ref "D134") (pin "C") (pinfunction "C_C") (pintype "passive"))
      (node (ref "Q11") (pin "3") (pinfunction "C_3") (pintype "passive"))
      (node (ref "R71") (pin "2") (pinfunction "2_2") (pintype "passive"))
      (node (ref "U$1") (pin "AH2") (pinfunction "1_AH2") (pintype "bidirectional"))
    )
    (net (code "21") (name "/MB2MA") (class "Default")
      (node (ref "D14") (pin "A") (pinfunction "A_A") (pintype "passive"))
      (node (ref "D89") (pin "A") (pinfunction "A_A") (pintype "passive"))
      (node (ref "D90") (pin "A") (pinfunction "A_A") (pintype "passive"))
      (node (ref "U$1") (pin "AN2") (pinfunction "1_AN2") (pintype "bidirectional"))
    )
    (net (code "22") (name "/MB2PC") (class "Default")
      (node (ref "D3") (pin "A") (pinfunction "A_A") (pintype "passive"))
      (node (ref "D77") (pin "A") (pinfunction "A_A") (pintype "passive"))
      (node (ref "D84") (pin "A") (pinfunction "A_A") (pintype "passive"))
      (node (ref "U$1") (pin "BA2") (pinfunction "1_BA2") (pintype "bidirectional"))
    )
    (net (code "23") (name "/MB=0") (class "Default")
      (node (ref "C21") (pin "2") (pinfunction "2_2") (pintype "passive"))
      (node (ref "D61") (pin "C") (pinfunction "C_C") (pintype "passive"))
      (node (ref "D62") (pin "A") (pinfunction "A_A") (pintype "passive"))
      (node (ref "D78") (pin "A") (pinfunction "A_A") (pintype "passive"))
      (node (ref "D87") (pin "A") (pinfunction "A_A") (pintype "passive"))
      (node (ref "D95") (pin "A") (pinfunction "A_A") (pintype "passive"))
      (node (ref "D98") (pin "A") (pinfunction "A_A") (pintype "passive"))
      (node (ref "Q5") (pin "3") (pinfunction "C_3") (pintype "passive"))
      (node (ref "R31") (pin "2") (pinfunction "2_2") (pintype "passive"))
      (node (ref "R70") (pin "2") (pinfunction "2_2") (pintype "passive"))
    )
    (net (code "24") (name "/MB=1") (class "Default")
      (node (ref "C22") (pin "2") (pinfunction "2_2") (pintype "passive"))
      (node (ref "D21") (pin "A") (pinfunction "A_A") (pintype "passive"))
      (node (ref "D22") (pin "A") (pinfunction "A_A") (pintype "passive"))
      (node (ref "D27") (pin "A") (pinfunction "A_A") (pintype "passive"))
      (node (ref "D52") (pin "C") (pinfunction "C_C") (pintype "passive"))
      (node (ref "D53") (pin "A") (pinfunction "A_A") (pintype "passive"))
      (node (ref "D9") (pin "A") (pinfunction "A_A") (pintype "passive"))
      (node (ref "Q7") (pin "3") (pinfunction "C_3") (pintype "passive"))
      (node (ref "R29") (pin "2") (pinfunction "2_2") (pintype "passive"))
      (node (ref "R74") (pin "2") (pinfunction "2_2") (pintype "passive"))
    )
    (net (code "25") (name "/MBCARRYENA") (class "Default")
      (node (ref "D25") (pin "A") (pinfunction "A_A") (pintype "passive"))
      (node (ref "D36") (pin "A") (pinfunction "A_A") (pintype "passive"))
      (node (ref "D88") (pin "A") (pinfunction "A_A") (pintype "passive"))
      (node (ref "U$1") (pin "BH2") (pinfunction "1_BH2") (pintype "bidirectional"))
    )
    (net (code "26") (name "/MBOUT0") (class "Default")
      (node (ref "D136") (pin "C") (pinfunction "C_C") (pintype "passive"))
      (node (ref "Q13") (pin "3") (pinfunction "C_3") (pintype "passive"))
      (node (ref "R75") (pin "2") (pinfunction "2_2") (pintype "passive"))
      (node (ref "U$1") (pin "AD2") (pinfunction "1_AD2") (pintype "bidirectional"))
    )
    (net (code "27") (name "/MBOUT1") (class "Default")
      (node (ref "D135") (pin "C") (pinfunction "C_C") (pintype "passive"))
      (node (ref "Q12") (pin "3") (pinfunction "C_3") (pintype "passive"))
      (node (ref "R73") (pin "2") (pinfunction "2_2") (pintype "passive"))
      (node (ref "U$1") (pin "AF2") (pinfunction "1_AF2") (pintype "bidirectional"))
    )
    (net (code "28") (name "/PC2MA") (class "Default")
      (node (ref "D29") (pin "A") (pinfunction "A_A") (pintype "passive"))
      (node (ref "D76") (pin "A") (pinfunction "A_A") (pintype "passive"))
      (node (ref "D79") (pin "A") (pinfunction "A_A") (pintype "passive"))
      (node (ref "U$1") (pin "AM2") (pinfunction "1_AM2") (pintype "bidirectional"))
    )
    (net (code "29") (name "/PC2MB") (class "Default")
      (node (ref "D114") (pin "A") (pinfunction "A_A") (pintype "passive"))
      (node (ref "D115") (pin "A") (pinfunction "A_A") (pintype "passive"))
      (node (ref "D12") (pin "A") (pinfunction "A_A") (pintype "passive"))
      (node (ref "U$1") (pin "BV2") (pinfunction "1_BV2") (pintype "bidirectional"))
    )
    (net (code "30") (name "/PC=0") (class "Default")
      (node (ref "D120") (pin "A") (pinfunction "A_A") (pintype "passive"))
      (node (ref "D121") (pin "A") (pinfunction "A_A") (pintype "passive"))
      (node (ref "D50") (pin "C") (pinfunction "C_C") (pintype "passive"))
      (node (ref "D51") (pin "A") (pinfunction "A_A") (pintype "passive"))
      (node (ref "D59") (pin "A") (pinfunction "A_A") (pintype "passive"))
      (node (ref "D86") (pin "A") (pinfunction "A_A") (pintype "passive"))
      (node (ref "Q2") (pin "3") (pinfunction "C_3") (pintype "passive"))
      (node (ref "R23") (pin "2") (pinfunction "2_2") (pintype "passive"))
      (node (ref "U$1") (pin "BL2") (pinfunction "1_BL2") (pintype "bidirectional"))
    )
    (net (code "31") (name "/PC=1") (class "Default")
      (node (ref "D13") (pin "A") (pinfunction "A_A") (pintype "passive"))
      (node (ref "D18") (pin "A") (pinfunction "A_A") (pintype "passive"))
      (node (ref "D24") (pin "A") (pinfunction "A_A") (pintype "passive"))
      (node (ref "D37") (pin "A") (pinfunction "A_A") (pintype "passive"))
      (node (ref "D38") (pin "C") (pinfunction "C_C") (pintype "passive"))
      (node (ref "D39") (pin "A") (pinfunction "A_A") (pintype "passive"))
      (node (ref "Q3") (pin "3") (pinfunction "C_3") (pintype "passive"))
      (node (ref "R20") (pin "2") (pinfunction "2_2") (pintype "passive"))
      (node (ref "U$1") (pin "BK2") (pinfunction "1_BK2") (pintype "bidirectional"))
    )
    (net (code "32") (name "/SET_MA") (class "Default")
      (node (ref "D69") (pin "A") (pinfunction "A_A") (pintype "passive"))
      (node (ref "U$1") (pin "AK2") (pinfunction "1_AK2") (pintype "bidirectional"))
    )
    (net (code "33") (name "/SET_MB") (class "Default")
      (node (ref "D70") (pin "A") (pinfunction "A_A") (pintype "passive"))
      (node (ref "D74") (pin "C") (pinfunction "C_C") (pintype "passive"))
      (node (ref "R38") (pin "2") (pinfunction "2_2") (pintype "passive"))
      (node (ref "U$1") (pin "AT2") (pinfunction "1_AT2") (pintype "bidirectional"))
    )
    (net (code "34") (name "/SHIFT") (class "Default")
      (node (ref "D123") (pin "A") (pinfunction "A_A") (pintype "passive"))
      (node (ref "D124") (pin "A") (pinfunction "A_A") (pintype "passive"))
      (node (ref "D4") (pin "A") (pinfunction "A_A") (pintype "passive"))
      (node (ref "U$1") (pin "BU2") (pinfunction "1_BU2") (pintype "bidirectional"))
    )
    (net (code "35") (name "/SR") (class "Default")
      (node (ref "D101") (pin "A") (pinfunction "A_A") (pintype "passive"))
      (node (ref "D104") (pin "A") (pinfunction "A_A") (pintype "passive"))
      (node (ref "U$1") (pin "BF2") (pinfunction "1_BF2") (pintype "bidirectional"))
    )
    (net (code "36") (name "/SR2PC") (class "Default")
      (node (ref "D91") (pin "A") (pinfunction "A_A") (pintype "passive"))
      (node (ref "D92") (pin "A") (pinfunction "A_A") (pintype "passive"))
      (node (ref "U$1") (pin "BB2") (pinfunction "1_BB2") (pintype "bidirectional"))
    )
    (net (code "37") (name "GND") (class "Default")
      (node (ref "C18") (pin "1") (pinfunction "1_1") (pintype "passive"))
      (node (ref "D113") (pin "A") (pinfunction "A_A") (pintype "passive"))
      (node (ref "Q10") (pin "1") (pinfunction "E_1") (pintype "passive"))
      (node (ref "Q11") (pin "1") (pinfunction "E_1") (pintype "passive"))
      (node (ref "Q12") (pin "1") (pinfunction "E_1") (pintype "passive"))
      (node (ref "Q13") (pin "1") (pinfunction "E_1") (pintype "passive"))
      (node (ref "Q2") (pin "1") (pinfunction "E_1") (pintype "passive"))
      (node (ref "Q3") (pin "1") (pinfunction "E_1") (pintype "passive"))
      (node (ref "Q4") (pin "1") (pinfunction "E_1") (pintype "passive"))
      (node (ref "Q5") (pin "1") (pinfunction "E_1") (pintype "passive"))
      (node (ref "Q6") (pin "1") (pinfunction "E_1") (pintype "passive"))
      (node (ref "Q7") (pin "1") (pinfunction "E_1") (pintype "passive"))
      (node (ref "Q9") (pin "1") (pinfunction "E_1") (pintype "passive"))
      (node (ref "U$1") (pin "AC2") (pinfunction "1_AC2") (pintype "bidirectional"))
      (node (ref "U$1") (pin "BC2") (pinfunction "1_BC2") (pintype "bidirectional"))
    )
    (net (code "38") (name "Net-(C1-Pad1)") (class "Default")
      (node (ref "C1") (pin "1") (pinfunction "1_1") (pintype "passive"))
      (node (ref "D2") (pin "C") (pinfunction "C_C") (pintype "passive"))
      (node (ref "R1") (pin "2") (pinfunction "2_2") (pintype "passive"))
    )
    (net (code "39") (name "Net-(C1-Pad2)") (class "Default")
      (node (ref "C1") (pin "2") (pinfunction "2_2") (pintype "passive"))
      (node (ref "D5") (pin "A") (pinfunction "A_A") (pintype "passive"))
      (node (ref "D8") (pin "C") (pinfunction "C_C") (pintype "passive"))
      (node (ref "R4") (pin "2") (pinfunction "2_2") (pintype "passive"))
    )
    (net (code "40") (name "Net-(C2-Pad1)") (class "Default")
      (node (ref "C2") (pin "1") (pinfunction "1_1") (pintype "passive"))
      (node (ref "D3") (pin "C") (pinfunction "C_C") (pintype "passive"))
      (node (ref "R2") (pin "2") (pinfunction "2_2") (pintype "passive"))
    )
    (net (code "41") (name "Net-(C2-Pad2)") (class "Default")
      (node (ref "C2") (pin "2") (pinfunction "2_2") (pintype "passive"))
      (node (ref "D6") (pin "A") (pinfunction "A_A") (pintype "passive"))
      (node (ref "D9") (pin "C") (pinfunction "C_C") (pintype "passive"))
      (node (ref "R5") (pin "2") (pinfunction "2_2") (pintype "passive"))
    )
    (net (code "42") (name "Net-(C3-Pad1)") (class "Default")
      (node (ref "C3") (pin "1") (pinfunction "1_1") (pintype "passive"))
      (node (ref "D4") (pin "C") (pinfunction "C_C") (pintype "passive"))
      (node (ref "R3") (pin "2") (pinfunction "2_2") (pintype "passive"))
    )
    (net (code "43") (name "Net-(C3-Pad2)") (class "Default")
      (node (ref "C3") (pin "2") (pinfunction "2_2") (pintype "passive"))
      (node (ref "D10") (pin "C") (pinfunction "C_C") (pintype "passive"))
      (node (ref "D7") (pin "A") (pinfunction "A_A") (pintype "passive"))
      (node (ref "R6") (pin "2") (pinfunction "2_2") (pintype "passive"))
    )
    (net (code "44") (name "Net-(C4-Pad1)") (class "Default")
      (node (ref "C4") (pin "1") (pinfunction "1_1") (pintype "passive"))
      (node (ref "D12") (pin "C") (pinfunction "C_C") (pintype "passive"))
      (node (ref "R7") (pin "2") (pinfunction "2_2") (pintype "passive"))
    )
    (net (code "45") (name "Net-(C4-Pad2)") (class "Default")
      (node (ref "C4") (pin "2") (pinfunction "2_2") (pintype "passive"))
      (node (ref "D16") (pin "A") (pinfunction "A_A") (pintype "passive"))
      (node (ref "D18") (pin "C") (pinfunction "C_C") (pintype "passive"))
      (node (ref "R10") (pin "2") (pinfunction "2_2") (pintype "passive"))
    )
    (net (code "46") (name "Net-(C5-Pad1)") (class "Default")
      (node (ref "C5") (pin "1") (pinfunction "1_1") (pintype "passive"))
      (node (ref "D14") (pin "C") (pinfunction "C_C") (pintype "passive"))
      (node (ref "R8") (pin "2") (pinfunction "2_2") (pintype "passive"))
    )
    (net (code "47") (name "Net-(C5-Pad2)") (class "Default")
      (node (ref "C5") (pin "2") (pinfunction "2_2") (pintype "passive"))
      (node (ref "D19") (pin "A") (pinfunction "A_A") (pintype "passive"))
      (node (ref "D21") (pin "C") (pinfunction "C_C") (pintype "passive"))
      (node (ref "R11") (pin "2") (pinfunction "2_2") (pintype "passive"))
    )
    (net (code "48") (name "Net-(C6-Pad1)") (class "Default")
      (node (ref "C6") (pin "1") (pinfunction "1_1") (pintype "passive"))
      (node (ref "D13") (pin "C") (pinfunction "C_C") (pintype "passive"))
      (node (ref "D15") (pin "C") (pinfunction "C_C") (pintype "passive"))
      (node (ref "D17") (pin "A") (pinfunction "A_A") (pintype "passive"))
      (node (ref "R9") (pin "2") (pinfunction "2_2") (pintype "passive"))
    )
    (net (code "49") (name "Net-(C6-Pad2)") (class "Default")
      (node (ref "C6") (pin "2") (pinfunction "2_2") (pintype "passive"))
      (node (ref "D17") (pin "C") (pinfunction "C_C") (pintype "passive"))
      (node (ref "D20") (pin "A") (pinfunction "A_A") (pintype "passive"))
      (node (ref "D23") (pin "C") (pinfunction "C_C") (pintype "passive"))
      (node (ref "R12") (pin "2") (pinfunction "2_2") (pintype "passive"))
    )
    (net (code "50") (name "Net-(C7-Pad1)") (class "Default")
      (node (ref "C7") (pin "1") (pinfunction "1_1") (pintype "passive"))
      (node (ref "D26") (pin "C") (pinfunction "C_C") (pintype "passive"))
      (node (ref "D27") (pin "C") (pinfunction "C_C") (pintype "passive"))
      (node (ref "D28") (pin "A") (pinfunction "A_A") (pintype "passive"))
      (node (ref "R13") (pin "2") (pinfunction "2_2") (pintype "passive"))
    )
    (net (code "51") (name "Net-(C8-Pad1)") (class "Default")
      (node (ref "C8") (pin "1") (pinfunction "1_1") (pintype "passive"))
      (node (ref "D29") (pin "C") (pinfunction "C_C") (pintype "passive"))
      (node (ref "R14") (pin "2") (pinfunction "2_2") (pintype "passive"))
    )
    (net (code "52") (name "Net-(C8-Pad2)") (class "Default")
      (node (ref "C8") (pin "2") (pinfunction "2_2") (pintype "passive"))
      (node (ref "D33") (pin "A") (pinfunction "A_A") (pintype "passive"))
      (node (ref "D37") (pin "C") (pinfunction "C_C") (pintype "passive"))
      (node (ref "R18") (pin "2") (pinfunction "2_2") (pintype "passive"))
    )
    (net (code "53") (name "Net-(C9-Pad1)") (class "Default")
      (node (ref "C9") (pin "1") (pinfunction "1_1") (pintype "passive"))
      (node (ref "D59") (pin "C") (pinfunction "C_C") (pintype "passive"))
      (node (ref "D63") (pin "C") (pinfunction "C_C") (pintype "passive"))
      (node (ref "D66") (pin "A") (pinfunction "A_A") (pintype "passive"))
      (node (ref "R32") (pin "2") (pinfunction "2_2") (pintype "passive"))
    )
    (net (code "54") (name "Net-(C9-Pad2)") (class "Default")
      (node (ref "C9") (pin "2") (pinfunction "2_2") (pintype "passive"))
      (node (ref "D66") (pin "C") (pinfunction "C_C") (pintype "passive"))
      (node (ref "D72") (pin "A") (pinfunction "A_A") (pintype "passive"))
      (node (ref "D73") (pin "C") (pinfunction "C_C") (pintype "passive"))
      (node (ref "R37") (pin "2") (pinfunction "2_2") (pintype "passive"))
    )
    (net (code "55") (name "Net-(C10-Pad1)") (class "Default")
      (node (ref "C10") (pin "1") (pinfunction "1_1") (pintype "passive"))
      (node (ref "D76") (pin "C") (pinfunction "C_C") (pintype "passive"))
      (node (ref "R39") (pin "2") (pinfunction "2_2") (pintype "passive"))
    )
    (net (code "56") (name "Net-(C10-Pad2)") (class "Default")
      (node (ref "C10") (pin "2") (pinfunction "2_2") (pintype "passive"))
      (node (ref "D82") (pin "A") (pinfunction "A_A") (pintype "passive"))
      (node (ref "D86") (pin "C") (pinfunction "C_C") (pintype "passive"))
      (node (ref "R42") (pin "2") (pinfunction "2_2") (pintype "passive"))
    )
    (net (code "57") (name "Net-(C11-Pad1)") (class "Default")
      (node (ref "C11") (pin "1") (pinfunction "1_1") (pintype "passive"))
      (node (ref "D77") (pin "C") (pinfunction "C_C") (pintype "passive"))
      (node (ref "R40") (pin "2") (pinfunction "2_2") (pintype "passive"))
    )
    (net (code "58") (name "Net-(C11-Pad2)") (class "Default")
      (node (ref "C11") (pin "2") (pinfunction "2_2") (pintype "passive"))
      (node (ref "D83") (pin "A") (pinfunction "A_A") (pintype "passive"))
      (node (ref "D87") (pin "C") (pinfunction "C_C") (pintype "passive"))
      (node (ref "R43") (pin "2") (pinfunction "2_2") (pintype "passive"))
    )
    (net (code "59") (name "Net-(C12-Pad1)") (class "Default")
      (node (ref "C12") (pin "1") (pinfunction "1_1") (pintype "passive"))
      (node (ref "D78") (pin "C") (pinfunction "C_C") (pintype "passive"))
      (node (ref "D80") (pin "C") (pinfunction "C_C") (pintype "passive"))
      (node (ref "D85") (pin "A") (pinfunction "A_A") (pintype "passive"))
      (node (ref "R41") (pin "2") (pinfunction "2_2") (pintype "passive"))
    )
    (net (code "60") (name "Net-(C13-Pad1)") (class "Default")
      (node (ref "C13") (pin "1") (pinfunction "1_1") (pintype "passive"))
      (node (ref "D89") (pin "C") (pinfunction "C_C") (pintype "passive"))
      (node (ref "R45") (pin "2") (pinfunction "2_2") (pintype "passive"))
    )
    (net (code "61") (name "Net-(C13-Pad2)") (class "Default")
      (node (ref "C13") (pin "2") (pinfunction "2_2") (pintype "passive"))
      (node (ref "D94") (pin "A") (pinfunction "A_A") (pintype "passive"))
      (node (ref "D98") (pin "C") (pinfunction "C_C") (pintype "passive"))
      (node (ref "R46") (pin "2") (pinfunction "2_2") (pintype "passive"))
    )
    (net (code "62") (name "Net-(C14-Pad1)") (class "Default")
      (node (ref "C14") (pin "1") (pinfunction "1_1") (pintype "passive"))
      (node (ref "D91") (pin "C") (pinfunction "C_C") (pintype "passive"))
      (node (ref "R47") (pin "2") (pinfunction "2_2") (pintype "passive"))
    )
    (net (code "63") (name "Net-(C14-Pad2)") (class "Default")
      (node (ref "C14") (pin "2") (pinfunction "2_2") (pintype "passive"))
      (node (ref "D101") (pin "C") (pinfunction "C_C") (pintype "passive"))
      (node (ref "D99") (pin "A") (pinfunction "A_A") (pintype "passive"))
      (node (ref "R50") (pin "2") (pinfunction "2_2") (pintype "passive"))
    )
    (net (code "64") (name "Net-(C15-Pad1)") (class "Default")
      (node (ref "C15") (pin "1") (pinfunction "1_1") (pintype "passive"))
      (node (ref "D96") (pin "C") (pinfunction "C_C") (pintype "passive"))
      (node (ref "R49") (pin "2") (pinfunction "2_2") (pintype "passive"))
    )
    (net (code "65") (name "Net-(C15-Pad2)") (class "Default")
      (node (ref "C15") (pin "2") (pinfunction "2_2") (pintype "passive"))
      (node (ref "D102") (pin "A") (pinfunction "A_A") (pintype "passive"))
      (node (ref "D106") (pin "C") (pinfunction "C_C") (pintype "passive"))
      (node (ref "R52") (pin "2") (pinfunction "2_2") (pintype "passive"))
    )
    (net (code "66") (name "Net-(C16-Pad1)") (class "Default")
      (node (ref "C16") (pin "1") (pinfunction "1_1") (pintype "passive"))
      (node (ref "D100") (pin "C") (pinfunction "C_C") (pintype "passive"))
      (node (ref "R51") (pin "2") (pinfunction "2_2") (pintype "passive"))
    )
    (net (code "67") (name "Net-(C16-Pad2)") (class "Default")
      (node (ref "C16") (pin "2") (pinfunction "2_2") (pintype "passive"))
      (node (ref "D105") (pin "A") (pinfunction "A_A") (pintype "passive"))
      (node (ref "D108") (pin "C") (pinfunction "C_C") (pintype "passive"))
      (node (ref "R53") (pin "2") (pinfunction "2_2") (pintype "passive"))
    )
    (net (code "68") (name "Net-(C17-Pad1)") (class "Default")
      (node (ref "C17") (pin "1") (pinfunction "1_1") (pintype "passive"))
      (node (ref "D114") (pin "C") (pinfunction "C_C") (pintype "passive"))
      (node (ref "R55") (pin "2") (pinfunction "2_2") (pintype "passive"))
    )
    (net (code "69") (name "Net-(C17-Pad2)") (class "Default")
      (node (ref "C17") (pin "2") (pinfunction "2_2") (pintype "passive"))
      (node (ref "D117") (pin "A") (pinfunction "A_A") (pintype "passive"))
      (node (ref "D120") (pin "C") (pinfunction "C_C") (pintype "passive"))
      (node (ref "R56") (pin "2") (pinfunction "2_2") (pintype "passive"))
    )
    (net (code "70") (name "Net-(C19-Pad1)") (class "Default")
      (node (ref "C19") (pin "1") (pinfunction "1_1") (pintype "passive"))
      (node (ref "D123") (pin "C") (pinfunction "C_C") (pintype "passive"))
      (node (ref "R60") (pin "2") (pinfunction "2_2") (pintype "passive"))
    )
    (net (code "71") (name "Net-(C19-Pad2)") (class "Default")
      (node (ref "C19") (pin "2") (pinfunction "2_2") (pintype "passive"))
      (node (ref "D125") (pin "A") (pinfunction "A_A") (pintype "passive"))
      (node (ref "D126") (pin "C") (pinfunction "C_C") (pintype "passive"))
      (node (ref "R62") (pin "2") (pinfunction "2_2") (pintype "passive"))
    )
    (net (code "72") (name "Net-(C20-Pad1)") (class "Default")
      (node (ref "C20") (pin "1") (pinfunction "1_1") (pintype "passive"))
      (node (ref "D129") (pin "C") (pinfunction "C_C") (pintype "passive"))
      (node (ref "R64") (pin "2") (pinfunction "2_2") (pintype "passive"))
    )
    (net (code "73") (name "Net-(C20-Pad2)") (class "Default")
      (node (ref "C20") (pin "2") (pinfunction "2_2") (pintype "passive"))
      (node (ref "D131") (pin "A") (pinfunction "A_A") (pintype "passive"))
      (node (ref "D132") (pin "C") (pinfunction "C_C") (pintype "passive"))
      (node (ref "R67") (pin "2") (pinfunction "2_2") (pintype "passive"))
    )
    (net (code "74") (name "Net-(D16-PadC)") (class "Default")
      (node (ref "D16") (pin "C") (pinfunction "C_C") (pintype "passive"))
      (node (ref "D32") (pin "A") (pinfunction "A_A") (pintype "passive"))
      (node (ref "D7") (pin "C") (pinfunction "C_C") (pintype "passive"))
    )
    (net (code "75") (name "Net-(D19-PadC)") (class "Default")
      (node (ref "D19") (pin "C") (pinfunction "C_C") (pintype "passive"))
      (node (ref "D33") (pin "C") (pinfunction "C_C") (pintype "passive"))
      (node (ref "D42") (pin "A") (pinfunction "A_A") (pintype "passive"))
      (node (ref "D5") (pin "C") (pinfunction "C_C") (pintype "passive"))
    )
    (net (code "76") (name "Net-(D20-PadC)") (class "Default")
      (node (ref "D20") (pin "C") (pinfunction "C_C") (pintype "passive"))
      (node (ref "D31") (pin "A") (pinfunction "A_A") (pintype "passive"))
      (node (ref "D6") (pin "C") (pinfunction "C_C") (pintype "passive"))
    )
    (net (code "77") (name "Net-(D30-PadC)") (class "Default")
      (node (ref "D30") (pin "C") (pinfunction "C_C") (pintype "passive"))
      (node (ref "D34") (pin "C") (pinfunction "C_C") (pintype "passive"))
      (node (ref "D39") (pin "C") (pinfunction "C_C") (pintype "passive"))
      (node (ref "R16") (pin "2") (pinfunction "2_2") (pintype "passive"))
    )
    (net (code "78") (name "Net-(D34-PadA)") (class "Default")
      (node (ref "D34") (pin "A") (pinfunction "A_A") (pintype "passive"))
      (node (ref "D35") (pin "C") (pinfunction "C_C") (pintype "passive"))
    )
    (net (code "79") (name "Net-(D40-PadC)") (class "Default")
      (node (ref "D40") (pin "C") (pinfunction "C_C") (pintype "passive"))
      (node (ref "D41") (pin "C") (pinfunction "C_C") (pintype "passive"))
      (node (ref "D44") (pin "C") (pinfunction "C_C") (pintype "passive"))
      (node (ref "D49") (pin "C") (pinfunction "C_C") (pintype "passive"))
      (node (ref "R21") (pin "2") (pinfunction "2_2") (pintype "passive"))
    )
    (net (code "80") (name "Net-(D43-PadC)") (class "Default")
      (node (ref "D43") (pin "C") (pinfunction "C_C") (pintype "passive"))
      (node (ref "D46") (pin "C") (pinfunction "C_C") (pintype "passive"))
      (node (ref "D53") (pin "C") (pinfunction "C_C") (pintype "passive"))
      (node (ref "R24") (pin "2") (pinfunction "2_2") (pintype "passive"))
    )
    (net (code "81") (name "Net-(D44-PadA)") (class "Default")
      (node (ref "D44") (pin "A") (pinfunction "A_A") (pintype "passive"))
      (node (ref "D45") (pin "C") (pinfunction "C_C") (pintype "passive"))
    )
    (net (code "82") (name "Net-(D46-PadA)") (class "Default")
      (node (ref "D46") (pin "A") (pinfunction "A_A") (pintype "passive"))
      (node (ref "D47") (pin "C") (pinfunction "C_C") (pintype "passive"))
    )
    (net (code "83") (name "Net-(D51-PadC)") (class "Default")
      (node (ref "D51") (pin "C") (pinfunction "C_C") (pintype "passive"))
      (node (ref "D54") (pin "C") (pinfunction "C_C") (pintype "passive"))
      (node (ref "R27") (pin "2") (pinfunction "2_2") (pintype "passive"))
    )
    (net (code "84") (name "Net-(D54-PadA)") (class "Default")
      (node (ref "D54") (pin "A") (pinfunction "A_A") (pintype "passive"))
      (node (ref "D55") (pin "C") (pinfunction "C_C") (pintype "passive"))
    )
    (net (code "85") (name "Net-(D56-PadA)") (class "Default")
      (node (ref "D56") (pin "A") (pinfunction "A_A") (pintype "passive"))
      (node (ref "D72") (pin "C") (pinfunction "C_C") (pintype "passive"))
      (node (ref "D83") (pin "C") (pinfunction "C_C") (pintype "passive"))
      (node (ref "D99") (pin "C") (pinfunction "C_C") (pintype "passive"))
    )
    (net (code "86") (name "Net-(D58-PadC)") (class "Default")
      (node (ref "D58") (pin "C") (pinfunction "C_C") (pintype "passive"))
      (node (ref "D64") (pin "C") (pinfunction "C_C") (pintype "passive"))
      (node (ref "D69") (pin "C") (pinfunction "C_C") (pintype "passive"))
      (node (ref "R33") (pin "2") (pinfunction "2_2") (pintype "passive"))
    )
    (net (code "87") (name "Net-(D62-PadC)") (class "Default")
      (node (ref "D62") (pin "C") (pinfunction "C_C") (pintype "passive"))
      (node (ref "D67") (pin "C") (pinfunction "C_C") (pintype "passive"))
      (node (ref "D70") (pin "C") (pinfunction "C_C") (pintype "passive"))
      (node (ref "R35") (pin "2") (pinfunction "2_2") (pintype "passive"))
    )
    (net (code "88") (name "Net-(D64-PadA)") (class "Default")
      (node (ref "D64") (pin "A") (pinfunction "A_A") (pintype "passive"))
      (node (ref "D65") (pin "C") (pinfunction "C_C") (pintype "passive"))
    )
    (net (code "89") (name "Net-(D67-PadA)") (class "Default")
      (node (ref "D67") (pin "A") (pinfunction "A_A") (pintype "passive"))
      (node (ref "D68") (pin "C") (pinfunction "C_C") (pintype "passive"))
    )
    (net (code "90") (name "Net-(D102-PadC)") (class "Default")
      (node (ref "D102") (pin "C") (pinfunction "C_C") (pintype "passive"))
      (node (ref "D117") (pin "C") (pinfunction "C_C") (pintype "passive"))
      (node (ref "D125") (pin "C") (pinfunction "C_C") (pintype "passive"))
      (node (ref "D131") (pin "C") (pinfunction "C_C") (pintype "passive"))
      (node (ref "D93") (pin "A") (pinfunction "A_A") (pintype "passive"))
    )
    (net (code "91") (name "Net-(D105-PadC)") (class "Default")
      (node (ref "D105") (pin "C") (pinfunction "C_C") (pintype "passive"))
      (node (ref "D71") (pin "A") (pinfunction "A_A") (pintype "passive"))
      (node (ref "D82") (pin "C") (pinfunction "C_C") (pintype "passive"))
      (node (ref "D94") (pin "C") (pinfunction "C_C") (pintype "passive"))
    )
    (net (code "92") (name "Net-(D110-PadA)") (class "Default")
      (node (ref "D110") (pin "A") (pinfunction "A_A") (pintype "passive"))
      (node (ref "D111") (pin "C") (pinfunction "C_C") (pintype "passive"))
    )
    (net (code "93") (name "Net-(D111-PadA)") (class "Default")
      (node (ref "D111") (pin "A") (pinfunction "A_A") (pintype "passive"))
      (node (ref "D112") (pin "C") (pinfunction "C_C") (pintype "passive"))
    )
    (net (code "94") (name "Net-(D116-PadC)") (class "Default")
      (node (ref "D116") (pin "C") (pinfunction "C_C") (pintype "passive"))
      (node (ref "D118") (pin "C") (pinfunction "C_C") (pintype "passive"))
      (node (ref "R57") (pin "2") (pinfunction "2_2") (pintype "passive"))
    )
    (net (code "95") (name "Net-(D118-PadA)") (class "Default")
      (node (ref "D118") (pin "A") (pinfunction "A_A") (pintype "passive"))
      (node (ref "D119") (pin "C") (pinfunction "C_C") (pintype "passive"))
    )
    (net (code "96") (name "Net-(Q1-B)") (class "Default")
      (node (ref "C7") (pin "2") (pinfunction "2_2") (pintype "passive"))
      (node (ref "D28") (pin "C") (pinfunction "C_C") (pintype "passive"))
      (node (ref "D36") (pin "C") (pinfunction "C_C") (pintype "passive"))
      (node (ref "Q1") (pin "2") (pinfunction "B_2") (pintype "passive"))
      (node (ref "R15") (pin "2") (pinfunction "2_2") (pintype "passive"))
    )
    (net (code "97") (name "Net-(Q1-C)") (class "Default")
      (node (ref "Q1") (pin "3") (pinfunction "C_3") (pintype "passive"))
      (node (ref "R19") (pin "1") (pinfunction "1_1") (pintype "passive"))
    )
    (net (code "98") (name "Net-(Q1-E)") (class "Default")
      (node (ref "D32") (pin "C") (pinfunction "C_C") (pintype "passive"))
      (node (ref "D47") (pin "A") (pinfunction "A_A") (pintype "passive"))
      (node (ref "Q1") (pin "1") (pinfunction "E_1") (pintype "passive"))
      (node (ref "Q5") (pin "2") (pinfunction "B_2") (pintype "passive"))
      (node (ref "R25") (pin "1") (pinfunction "1_1") (pintype "passive"))
    )
    (net (code "99") (name "Net-(Q2-B)") (class "Default")
      (node (ref "D31") (pin "C") (pinfunction "C_C") (pintype "passive"))
      (node (ref "D35") (pin "A") (pinfunction "A_A") (pintype "passive"))
      (node (ref "Q2") (pin "2") (pinfunction "B_2") (pintype "passive"))
      (node (ref "R17") (pin "1") (pinfunction "1_1") (pintype "passive"))
    )
    (net (code "100") (name "Net-(Q3-B)") (class "Default")
      (node (ref "D55") (pin "A") (pinfunction "A_A") (pintype "passive"))
      (node (ref "D56") (pin "C") (pinfunction "C_C") (pintype "passive"))
      (node (ref "Q3") (pin "2") (pinfunction "B_2") (pintype "passive"))
      (node (ref "R28") (pin "1") (pinfunction "1_1") (pintype "passive"))
    )
    (net (code "101") (name "Net-(Q4-B)") (class "Default")
      (node (ref "D42") (pin "C") (pinfunction "C_C") (pintype "passive"))
      (node (ref "D45") (pin "A") (pinfunction "A_A") (pintype "passive"))
      (node (ref "Q4") (pin "2") (pinfunction "B_2") (pintype "passive"))
      (node (ref "R22") (pin "1") (pinfunction "1_1") (pintype "passive"))
    )
    (net (code "102") (name "Net-(Q6-B)") (class "Default")
      (node (ref "D65") (pin "A") (pinfunction "A_A") (pintype "passive"))
      (node (ref "D71") (pin "C") (pinfunction "C_C") (pintype "passive"))
      (node (ref "Q6") (pin "2") (pinfunction "B_2") (pintype "passive"))
      (node (ref "R34") (pin "1") (pinfunction "1_1") (pintype "passive"))
    )
    (net (code "103") (name "Net-(Q7-B)") (class "Default")
      (node (ref "D68") (pin "A") (pinfunction "A_A") (pintype "passive"))
      (node (ref "D93") (pin "C") (pinfunction "C_C") (pintype "passive"))
      (node (ref "Q7") (pin "2") (pinfunction "B_2") (pintype "passive"))
      (node (ref "Q8") (pin "1") (pinfunction "E_1") (pintype "passive"))
      (node (ref "R36") (pin "1") (pinfunction "1_1") (pintype "passive"))
    )
    (net (code "104") (name "Net-(Q8-B)") (class "Default")
      (node (ref "C12") (pin "2") (pinfunction "2_2") (pintype "passive"))
      (node (ref "D85") (pin "C") (pinfunction "C_C") (pintype "passive"))
      (node (ref "D88") (pin "C") (pinfunction "C_C") (pintype "passive"))
      (node (ref "Q8") (pin "2") (pinfunction "B_2") (pintype "passive"))
      (node (ref "R44") (pin "2") (pinfunction "2_2") (pintype "passive"))
    )
    (net (code "105") (name "Net-(Q8-C)") (class "Default")
      (node (ref "Q8") (pin "3") (pinfunction "C_3") (pintype "passive"))
      (node (ref "R48") (pin "2") (pinfunction "2_2") (pintype "passive"))
    )
    (net (code "106") (name "Net-(Q9-B)") (class "Default")
      (node (ref "D119") (pin "A") (pinfunction "A_A") (pintype "passive"))
      (node (ref "Q9") (pin "2") (pinfunction "B_2") (pintype "passive"))
      (node (ref "R58") (pin "1") (pinfunction "1_1") (pintype "passive"))
    )
    (net (code "107") (name "Net-(Q9-C)") (class "Default")
      (node (ref "D11") (pin "A") (pinfunction "A_A") (pintype "passive"))
      (node (ref "D122") (pin "C") (pinfunction "C_C") (pintype "passive"))
      (node (ref "D8") (pin "A") (pinfunction "A_A") (pintype "passive"))
      (node (ref "Q9") (pin "3") (pinfunction "C_3") (pintype "passive"))
      (node (ref "R59") (pin "2") (pinfunction "2_2") (pintype "passive"))
    )
    (net (code "108") (name "Net-(Q10-B)") (class "Default")
      (node (ref "C23") (pin "1") (pinfunction "1_1") (pintype "passive"))
      (node (ref "Q10") (pin "2") (pinfunction "B_2") (pintype "passive"))
      (node (ref "R66") (pin "1") (pinfunction "1_1") (pintype "passive"))
    )
    (net (code "109") (name "Net-(Q11-B)") (class "Default")
      (node (ref "C24") (pin "1") (pinfunction "1_1") (pintype "passive"))
      (node (ref "Q11") (pin "2") (pinfunction "B_2") (pintype "passive"))
      (node (ref "R72") (pin "1") (pinfunction "1_1") (pintype "passive"))
    )
    (net (code "110") (name "Net-(Q12-B)") (class "Default")
      (node (ref "C21") (pin "1") (pinfunction "1_1") (pintype "passive"))
      (node (ref "Q12") (pin "2") (pinfunction "B_2") (pintype "passive"))
      (node (ref "R70") (pin "1") (pinfunction "1_1") (pintype "passive"))
    )
    (net (code "111") (name "Net-(Q13-B)") (class "Default")
      (node (ref "C22") (pin "1") (pinfunction "1_1") (pintype "passive"))
      (node (ref "Q13") (pin "2") (pinfunction "B_2") (pintype "passive"))
      (node (ref "R74") (pin "1") (pinfunction "1_1") (pintype "passive"))
    )
    (net (code "112") (name "Net-(U$1AB-1)") (class "Default")
      (node (ref "D108") (pin "A") (pinfunction "A_A") (pintype "passive"))
      (node (ref "D109") (pin "A") (pinfunction "A_A") (pintype "passive"))
      (node (ref "D116") (pin "A") (pinfunction "A_A") (pintype "passive"))
      (node (ref "D137") (pin "C") (pinfunction "C_C") (pintype "passive"))
      (node (ref "R61") (pin "2") (pinfunction "2_2") (pintype "passive"))
      (node (ref "U$1") (pin "AR2") (pinfunction "1_AR2") (pintype "bidirectional"))
    )
    (net (code "113") (name "Net-(U$1BJ-1)") (class "Default")
      (node (ref "D126") (pin "A") (pinfunction "A_A") (pintype "passive"))
      (node (ref "D128") (pin "A") (pinfunction "A_A") (pintype "passive"))
      (node (ref "U$1") (pin "BP2") (pinfunction "1_BP2") (pintype "bidirectional"))
    )
    (net (code "114") (name "Net-(U$1BL-1)") (class "Default")
      (node (ref "D1") (pin "A") (pinfunction "A_A") (pintype "passive"))
      (node (ref "D10") (pin "A") (pinfunction "A_A") (pintype "passive"))
      (node (ref "U$1") (pin "BR2") (pinfunction "1_BR2") (pintype "bidirectional"))
    )
  )
)
